# CPU_DRAM.net
KiCad netlist of a schematic drawn in Altium Designer
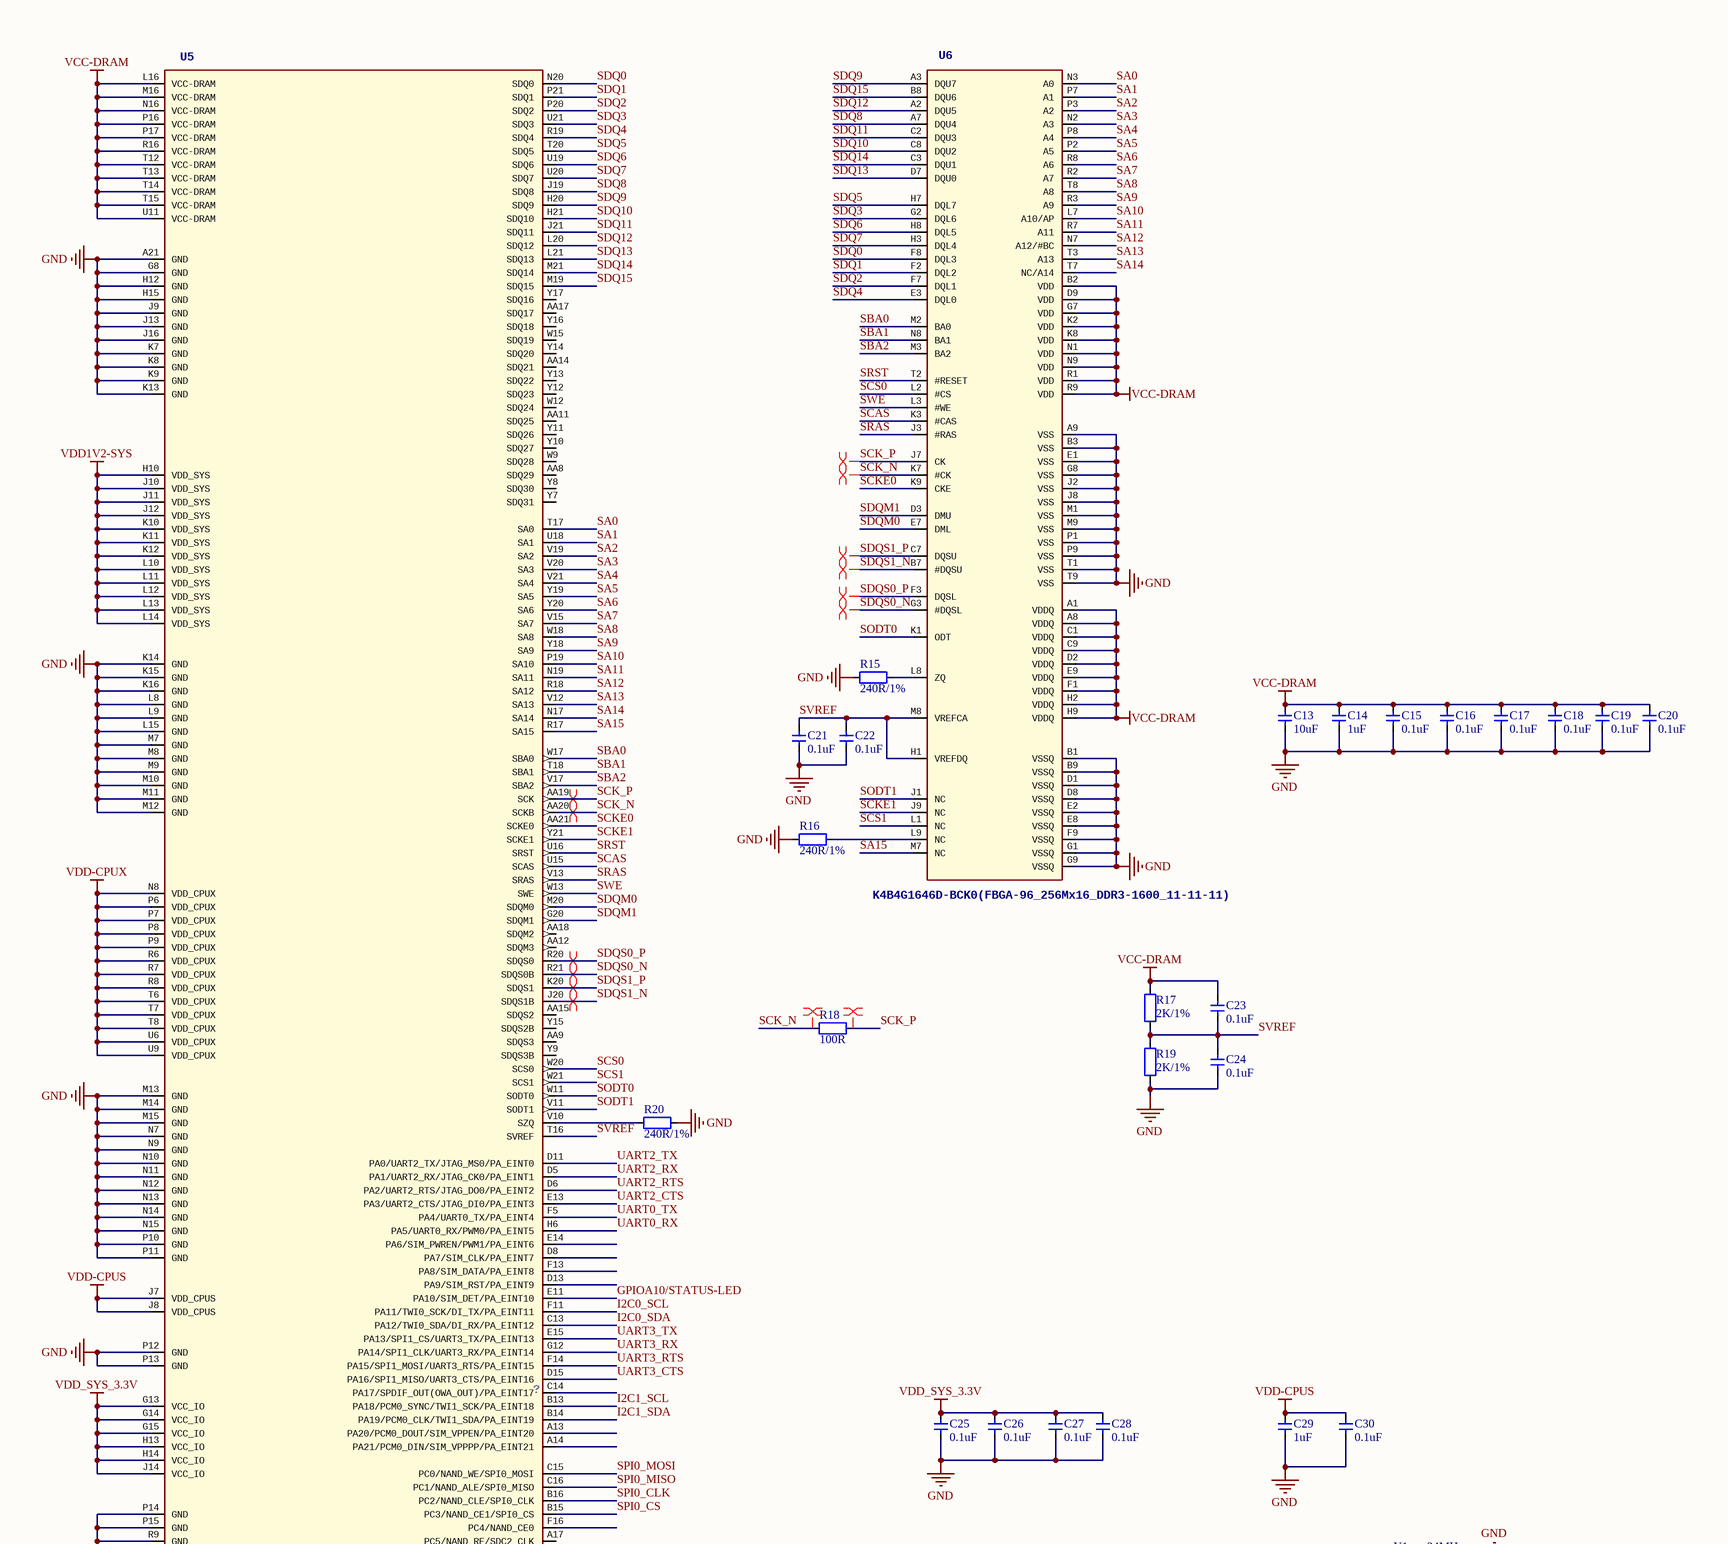
[diagram p0: CPU&DRAM.SchDoc, top]
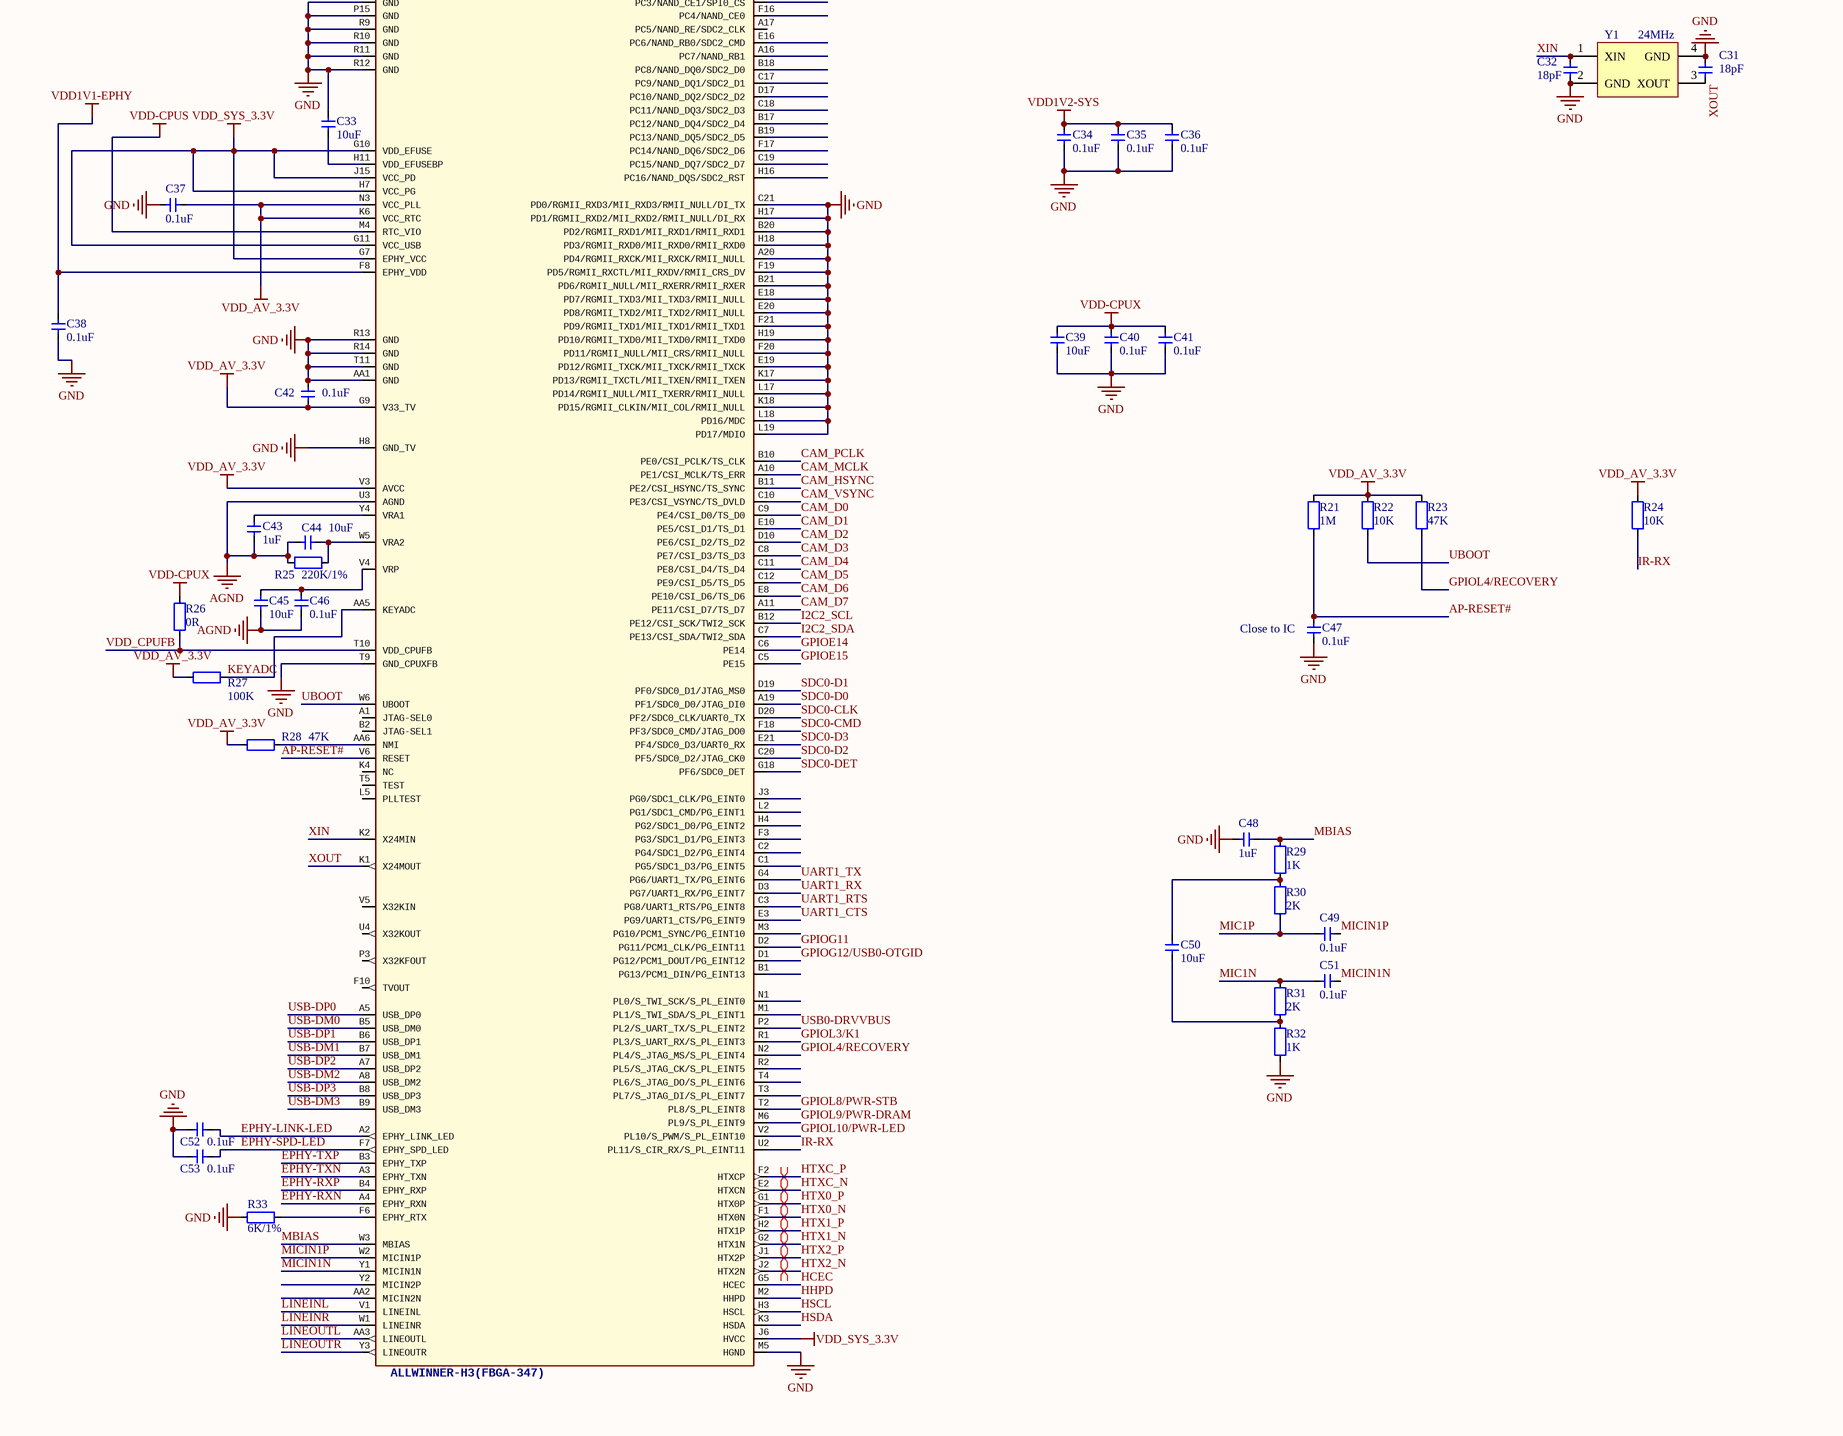
[diagram p1: CPU&DRAM.SchDoc, bottom]

(export (version "E")
  (design (tool "Eeschema 10.0.6"))
  (components
    (comp (ref "C13")
      (value "10uF")
      (footprint "CAP_0402")
      (description "Capacitor")
      (libsource (lib "MyPcbLib") (part "电容-0402"))
    )
    (comp (ref "C14")
      (value "1uF")
      (footprint "CAP_0402")
      (description "Capacitor")
      (libsource (lib "MyPcbLib") (part "电容-0402"))
    )
    (comp (ref "C15")
      (value "0.1uF")
      (footprint "CAP_0402")
      (description "Capacitor")
      (libsource (lib "MyPcbLib") (part "电容-0402"))
    )
    (comp (ref "C16")
      (value "0.1uF")
      (footprint "CAP_0402")
      (description "Capacitor")
      (libsource (lib "MyPcbLib") (part "电容-0402"))
    )
    (comp (ref "C17")
      (value "0.1uF")
      (footprint "CAP_0402")
      (description "Capacitor")
      (libsource (lib "MyPcbLib") (part "电容-0402"))
    )
    (comp (ref "C18")
      (value "0.1uF")
      (footprint "CAP_0402")
      (description "Capacitor")
      (libsource (lib "MyPcbLib") (part "电容-0402"))
    )
    (comp (ref "C19")
      (value "0.1uF")
      (footprint "CAP_0402")
      (description "Capacitor")
      (libsource (lib "MyPcbLib") (part "电容-0402"))
    )
    (comp (ref "C20")
      (value "0.1uF")
      (footprint "CAP_0402")
      (description "Capacitor")
      (libsource (lib "MyPcbLib") (part "电容-0402"))
    )
    (comp (ref "C21")
      (value "0.1uF")
      (footprint "CAP_0402")
      (description "Capacitor")
      (libsource (lib "MyPcbLib") (part "电容-0402"))
    )
    (comp (ref "C22")
      (value "0.1uF")
      (footprint "CAP_0402")
      (description "Capacitor")
      (libsource (lib "MyPcbLib") (part "电容-0402"))
    )
    (comp (ref "C23")
      (value "0.1uF")
      (footprint "CAP_0402")
      (description "Capacitor")
      (libsource (lib "MyPcbLib") (part "电容-0402"))
    )
    (comp (ref "C24")
      (value "0.1uF")
      (footprint "CAP_0402")
      (description "Capacitor")
      (libsource (lib "MyPcbLib") (part "电容-0402"))
    )
    (comp (ref "C25")
      (value "0.1uF")
      (footprint "CAP_0402")
      (description "Capacitor")
      (libsource (lib "MyPcbLib") (part "电容-0402"))
    )
    (comp (ref "C26")
      (value "0.1uF")
      (footprint "CAP_0402")
      (description "Capacitor")
      (libsource (lib "MyPcbLib") (part "电容-0402"))
    )
    (comp (ref "C27")
      (value "0.1uF")
      (footprint "CAP_0402")
      (description "Capacitor")
      (libsource (lib "MyPcbLib") (part "电容-0402"))
    )
    (comp (ref "C28")
      (value "0.1uF")
      (footprint "CAP_0402")
      (description "Capacitor")
      (libsource (lib "MyPcbLib") (part "电容-0402"))
    )
    (comp (ref "C29")
      (value "1uF")
      (footprint "CAP_0402")
      (description "Capacitor")
      (libsource (lib "MyPcbLib") (part "电容-0402"))
    )
    (comp (ref "C30")
      (value "0.1uF")
      (footprint "CAP_0402")
      (description "Capacitor")
      (libsource (lib "MyPcbLib") (part "电容-0402"))
    )
    (comp (ref "C31")
      (value "18pF")
      (footprint "CAP_0402")
      (description "Capacitor")
      (libsource (lib "MyPcbLib") (part "电容-0402"))
    )
    (comp (ref "C32")
      (value "18pF")
      (footprint "CAP_0402")
      (description "Capacitor")
      (libsource (lib "MyPcbLib") (part "电容-0402"))
    )
    (comp (ref "C33")
      (value "10uF")
      (footprint "CAP_0402")
      (description "Capacitor")
      (libsource (lib "MyPcbLib") (part "电容-0402"))
    )
    (comp (ref "C34")
      (value "0.1uF")
      (footprint "CAP_0402")
      (description "Capacitor")
      (libsource (lib "MyPcbLib") (part "电容-0402"))
    )
    (comp (ref "C35")
      (value "0.1uF")
      (footprint "CAP_0402")
      (description "Capacitor")
      (libsource (lib "MyPcbLib") (part "电容-0402"))
    )
    (comp (ref "C36")
      (value "0.1uF")
      (footprint "CAP_0402")
      (description "Capacitor")
      (libsource (lib "MyPcbLib") (part "电容-0402"))
    )
    (comp (ref "C37")
      (value "0.1uF")
      (footprint "CAP_0402")
      (description "Capacitor")
      (libsource (lib "MyPcbLib") (part "电容-0402"))
    )
    (comp (ref "C38")
      (value "0.1uF")
      (footprint "CAP_0402")
      (description "Capacitor")
      (libsource (lib "MyPcbLib") (part "电容-0402"))
    )
    (comp (ref "C39")
      (value "10uF")
      (footprint "CAP_0402")
      (description "Capacitor")
      (libsource (lib "MyPcbLib") (part "电容-0402"))
    )
    (comp (ref "C40")
      (value "0.1uF")
      (footprint "CAP_0402")
      (description "Capacitor")
      (libsource (lib "MyPcbLib") (part "电容-0402"))
    )
    (comp (ref "C41")
      (value "0.1uF")
      (footprint "CAP_0402")
      (description "Capacitor")
      (libsource (lib "MyPcbLib") (part "电容-0402"))
    )
    (comp (ref "C42")
      (value "0.1uF")
      (footprint "CAP_0402")
      (description "Capacitor")
      (libsource (lib "MyPcbLib") (part "电容-0402"))
    )
    (comp (ref "C43")
      (value "1uF")
      (footprint "CAP_0402")
      (description "Capacitor")
      (libsource (lib "MyPcbLib") (part "电容-0402"))
    )
    (comp (ref "C44")
      (value "10uF")
      (footprint "CAP_0402")
      (description "Capacitor")
      (libsource (lib "MyPcbLib") (part "电容-0402"))
    )
    (comp (ref "C45")
      (value "10uF")
      (footprint "CAP_0402")
      (description "Capacitor")
      (libsource (lib "MyPcbLib") (part "电容-0402"))
    )
    (comp (ref "C46")
      (value "0.1uF")
      (footprint "CAP_0402")
      (description "Capacitor")
      (libsource (lib "MyPcbLib") (part "电容-0402"))
    )
    (comp (ref "C47")
      (value "0.1uF")
      (footprint "CAP_0402")
      (description "Capacitor")
      (libsource (lib "MyPcbLib") (part "电容-0402"))
    )
    (comp (ref "C48")
      (value "1uF")
      (footprint "CAP_0402")
      (description "Capacitor")
      (libsource (lib "MyPcbLib") (part "电容-0402"))
    )
    (comp (ref "C49")
      (value "0.1uF")
      (footprint "CAP_0402")
      (description "Capacitor")
      (libsource (lib "MyPcbLib") (part "电容-0402"))
    )
    (comp (ref "C50")
      (value "10uF")
      (footprint "CAP_0402")
      (description "Capacitor")
      (libsource (lib "MyPcbLib") (part "电容-0402"))
    )
    (comp (ref "C51")
      (value "0.1uF")
      (footprint "CAP_0402")
      (description "Capacitor")
      (libsource (lib "MyPcbLib") (part "电容-0402"))
    )
    (comp (ref "C52")
      (value "0.1uF")
      (footprint "CAP_0402")
      (description "Capacitor")
      (libsource (lib "MyPcbLib") (part "电容-0402"))
    )
    (comp (ref "C53")
      (value "0.1uF")
      (footprint "CAP_0402")
      (description "Capacitor")
      (libsource (lib "MyPcbLib") (part "电容-0402"))
    )
    (comp (ref "R15")
      (value "240R/1%")
      (footprint "RES_0402")
      (description "Resistor")
      (libsource (lib "") (part "电阻-0402_2"))
    )
    (comp (ref "R16")
      (value "240R/1%")
      (footprint "RES_0402")
      (description "Resistor")
      (libsource (lib "") (part "电阻-0402_2"))
    )
    (comp (ref "R17")
      (value "2K/1%")
      (footprint "RES_0402")
      (description "Resistor")
      (libsource (lib "MyPcbLib") (part "电阻-0402"))
    )
    (comp (ref "R18")
      (value "100R")
      (footprint "RES_0402")
      (description "Resistor")
      (libsource (lib "") (part "电阻-0402_1"))
    )
    (comp (ref "R19")
      (value "2K/1%")
      (footprint "RES_0402")
      (description "Resistor")
      (libsource (lib "MyPcbLib") (part "电阻-0402"))
    )
    (comp (ref "R20")
      (value "240R/1%")
      (footprint "RES_0402")
      (description "Resistor")
      (libsource (lib "") (part "电阻-0402_1"))
    )
    (comp (ref "R21")
      (value "1M")
      (footprint "RES_0402")
      (description "Resistor")
      (libsource (lib "MyPcbLib") (part "电阻-0402"))
    )
    (comp (ref "R22")
      (value "10K")
      (footprint "RES_0402")
      (description "Resistor")
      (libsource (lib "MyPcbLib") (part "电阻-0402"))
    )
    (comp (ref "R23")
      (value "47K")
      (footprint "RES_0402")
      (description "Resistor")
      (libsource (lib "MyPcbLib") (part "电阻-0402"))
    )
    (comp (ref "R24")
      (value "10K")
      (footprint "RES_0402")
      (description "Resistor")
      (libsource (lib "MyPcbLib") (part "电阻-0402"))
    )
    (comp (ref "R25")
      (value "220K/1%")
      (footprint "RES_0402")
      (description "Resistor")
      (libsource (lib "") (part "电阻-0402_1"))
    )
    (comp (ref "R26")
      (value "0R")
      (footprint "RES_0402")
      (description "Resistor")
      (libsource (lib "MyPcbLib") (part "电阻-0402"))
    )
    (comp (ref "R27")
      (value "100K")
      (footprint "RES_0402")
      (description "Resistor")
      (libsource (lib "") (part "电阻-0402_1"))
    )
    (comp (ref "R28")
      (value "47K")
      (footprint "RES_0402")
      (description "Resistor")
      (libsource (lib "") (part "电阻-0402_1"))
    )
    (comp (ref "R29")
      (value "1K")
      (footprint "RES_0402")
      (description "Resistor")
      (libsource (lib "MyPcbLib") (part "电阻-0402"))
    )
    (comp (ref "R30")
      (value "2K")
      (footprint "RES_0402")
      (description "Resistor")
      (libsource (lib "MyPcbLib") (part "电阻-0402"))
    )
    (comp (ref "R31")
      (value "2K")
      (footprint "RES_0402")
      (description "Resistor")
      (libsource (lib "MyPcbLib") (part "电阻-0402"))
    )
    (comp (ref "R32")
      (value "1K")
      (footprint "RES_0402")
      (description "Resistor")
      (libsource (lib "MyPcbLib") (part "电阻-0402"))
    )
    (comp (ref "R33")
      (value "6K/1%")
      (footprint "RES_0402")
      (description "Resistor")
      (libsource (lib "") (part "电阻-0402_1"))
    )
    (comp (ref "U5")
      (value "ALLWINNER-H3(FBGA-347)")
      (footprint "FBGA-347")
      (fields (field (name "?") "?"))
      (libsource (lib "mLib") (part "ALLWINNER-H3(FBGA-347)"))
    )
    (comp (ref "U6")
      (value "K4B4G1646D-BCK0(FBGA-96_256Mx16_DDR3-1600_11-11-11)")
      (footprint "FBGA96(HYNIX_SAMSUNG_512MX16_DDR3)")
      (libsource (lib "mLib") (part "K4B8G1646Q-MYK0(FBGA-96_512MX16_DDR3-1600)"))
    )
    (comp (ref "Y1")
      (value "24MHz")
      (footprint "晶振2520")
      (description "2520无源")
      (fields (field (name "MF") "ECS International") (field (name "MP") "ECS-3225S30-240-EN-TR"))
      (libsource (lib "MyPcbLib") (part "晶振-4Pin-无源"))
    )
  )
  (nets
    (net (code "1") (name "/AP-RESET#") (class "Default")
      (node (ref "C47") (pin "2") (pinfunction "2_2") (pintype "passive"))
      (node (ref "R21") (pin "1") (pinfunction "1_1") (pintype "passive"))
      (node (ref "U5") (pin "V6") (pinfunction "RESET_V6") (pintype "passive"))
    )
    (net (code "2") (name "/CAM_D0") (class "Default")
      (node (ref "U5") (pin "C9") (pinfunction "PE4/CSI_D0/TS_D0_C9") (pintype "passive"))
    )
    (net (code "3") (name "/CAM_D1") (class "Default")
      (node (ref "U5") (pin "E10") (pinfunction "PE5/CSI_D1/TS_D1_E10") (pintype "passive"))
    )
    (net (code "4") (name "/CAM_D2") (class "Default")
      (node (ref "U5") (pin "D10") (pinfunction "PE6/CSI_D2/TS_D2_D10") (pintype "passive"))
    )
    (net (code "5") (name "/CAM_D3") (class "Default")
      (node (ref "U5") (pin "C8") (pinfunction "PE7/CSI_D3/TS_D3_C8") (pintype "passive"))
    )
    (net (code "6") (name "/CAM_D4") (class "Default")
      (node (ref "U5") (pin "C11") (pinfunction "PE8/CSI_D4/TS_D4_C11") (pintype "passive"))
    )
    (net (code "7") (name "/CAM_D5") (class "Default")
      (node (ref "U5") (pin "C12") (pinfunction "PE9/CSI_D5/TS_D5_C12") (pintype "passive"))
    )
    (net (code "8") (name "/CAM_D6") (class "Default")
      (node (ref "U5") (pin "E8") (pinfunction "PE10/CSI_D6/TS_D6_E8") (pintype "passive"))
    )
    (net (code "9") (name "/CAM_D7") (class "Default")
      (node (ref "U5") (pin "A11") (pinfunction "PE11/CSI_D7/TS_D7_A11") (pintype "passive"))
    )
    (net (code "10") (name "/CAM_HSYNC") (class "Default")
      (node (ref "U5") (pin "B11") (pinfunction "PE2/CSI_HSYNC/TS_SYNC_B11") (pintype "passive"))
    )
    (net (code "11") (name "/CAM_MCLK") (class "Default")
      (node (ref "U5") (pin "A10") (pinfunction "PE1/CSI_MCLK/TS_ERR_A10") (pintype "passive"))
    )
    (net (code "12") (name "/CAM_PCLK") (class "Default")
      (node (ref "U5") (pin "B10") (pinfunction "PE0/CSI_PCLK/TS_CLK_B10") (pintype "passive"))
    )
    (net (code "13") (name "/CAM_VSYNC") (class "Default")
      (node (ref "U5") (pin "C10") (pinfunction "PE3/CSI_VSYNC/TS_DVLD_C10") (pintype "passive"))
    )
    (net (code "14") (name "/EPHY-LINK-LED") (class "Default")
      (node (ref "C52") (pin "2") (pinfunction "2_2") (pintype "passive"))
      (node (ref "U5") (pin "A2") (pinfunction "EPHY_LINK_LED_A2") (pintype "output"))
    )
    (net (code "15") (name "/EPHY-RXN") (class "Default")
      (node (ref "U5") (pin "A4") (pinfunction "EPHY_RXN_A4") (pintype "passive"))
    )
    (net (code "16") (name "/EPHY-RXP") (class "Default")
      (node (ref "U5") (pin "B4") (pinfunction "EPHY_RXP_B4") (pintype "passive"))
    )
    (net (code "17") (name "/EPHY-SPD-LED") (class "Default")
      (node (ref "C53") (pin "2") (pinfunction "2_2") (pintype "passive"))
      (node (ref "U5") (pin "F7") (pinfunction "EPHY_SPD_LED_F7") (pintype "output"))
    )
    (net (code "18") (name "/EPHY-TXN") (class "Default")
      (node (ref "U5") (pin "A3") (pinfunction "EPHY_TXN_A3") (pintype "passive"))
    )
    (net (code "19") (name "/EPHY-TXP") (class "Default")
      (node (ref "U5") (pin "B3") (pinfunction "EPHY_TXP_B3") (pintype "passive"))
    )
    (net (code "20") (name "/GPIOA10{slash}STATUS-LED") (class "Default")
      (node (ref "U5") (pin "E11") (pinfunction "PA10/SIM_DET/PA_EINT10_E11") (pintype "passive"))
    )
    (net (code "21") (name "/GPIOE14") (class "Default")
      (node (ref "U5") (pin "C6") (pinfunction "PE14_C6") (pintype "passive"))
    )
    (net (code "22") (name "/GPIOE15") (class "Default")
      (node (ref "U5") (pin "C5") (pinfunction "PE15_C5") (pintype "passive"))
    )
    (net (code "23") (name "/GPIOG11") (class "Default")
      (node (ref "U5") (pin "D2") (pinfunction "PG11/PCM1_CLK/PG_EINT11_D2") (pintype "passive"))
    )
    (net (code "24") (name "/GPIOG12{slash}USB0-OTGID") (class "Default")
      (node (ref "U5") (pin "D1") (pinfunction "PG12/PCM1_DOUT/PG_EINT12_D1") (pintype "passive"))
    )
    (net (code "25") (name "/GPIOL3{slash}K1") (class "Default")
      (node (ref "U5") (pin "R1") (pinfunction "PL3/S_UART_RX/S_PL_EINT3_R1") (pintype "passive"))
    )
    (net (code "26") (name "/GPIOL4{slash}RECOVERY") (class "Default")
      (node (ref "R23") (pin "1") (pinfunction "1_1") (pintype "passive"))
      (node (ref "U5") (pin "N2") (pinfunction "PL4/S_JTAG_MS/S_PL_EINT4_N2") (pintype "passive"))
    )
    (net (code "27") (name "/GPIOL8{slash}PWR-STB") (class "Default")
      (node (ref "U5") (pin "T2") (pinfunction "PL8/S_PL_EINT8_T2") (pintype "passive"))
    )
    (net (code "28") (name "/GPIOL9{slash}PWR-DRAM") (class "Default")
      (node (ref "U5") (pin "M6") (pinfunction "PL9/S_PL_EINT9_M6") (pintype "passive"))
    )
    (net (code "29") (name "/GPIOL10{slash}PWR-LED") (class "Default")
      (node (ref "U5") (pin "V2") (pinfunction "PL10/S_PWM/S_PL_EINT10_V2") (pintype "passive"))
    )
    (net (code "30") (name "/HCEC") (class "Default")
      (node (ref "U5") (pin "G5") (pinfunction "HCEC_G5") (pintype "passive"))
    )
    (net (code "31") (name "/HHPD") (class "Default")
      (node (ref "U5") (pin "M2") (pinfunction "HHPD_M2") (pintype "passive"))
    )
    (net (code "32") (name "/HSCL") (class "Default")
      (node (ref "U5") (pin "H3") (pinfunction "HSCL_H3") (pintype "output"))
    )
    (net (code "33") (name "/HSDA") (class "Default")
      (node (ref "U5") (pin "K3") (pinfunction "HSDA_K3") (pintype "passive"))
    )
    (net (code "34") (name "/HTX0_N") (class "Default")
      (node (ref "U5") (pin "F1") (pinfunction "HTX0N_F1") (pintype "output"))
    )
    (net (code "35") (name "/HTX0_P") (class "Default")
      (node (ref "U5") (pin "G1") (pinfunction "HTX0P_G1") (pintype "output"))
    )
    (net (code "36") (name "/HTX1_N") (class "Default")
      (node (ref "U5") (pin "G2") (pinfunction "HTX1N_G2") (pintype "output"))
    )
    (net (code "37") (name "/HTX1_P") (class "Default")
      (node (ref "U5") (pin "H2") (pinfunction "HTX1P_H2") (pintype "output"))
    )
    (net (code "38") (name "/HTX2_N") (class "Default")
      (node (ref "U5") (pin "J2") (pinfunction "HTX2N_J2") (pintype "output"))
    )
    (net (code "39") (name "/HTX2_P") (class "Default")
      (node (ref "U5") (pin "J1") (pinfunction "HTX2P_J1") (pintype "output"))
    )
    (net (code "40") (name "/HTXC_N") (class "Default")
      (node (ref "U5") (pin "E2") (pinfunction "HTXCN_E2") (pintype "output"))
    )
    (net (code "41") (name "/HTXC_P") (class "Default")
      (node (ref "U5") (pin "F2") (pinfunction "HTXCP_F2") (pintype "output"))
    )
    (net (code "42") (name "/I2C0_SCL") (class "Default")
      (node (ref "U5") (pin "F11") (pinfunction "PA11/TWI0_SCK/DI_TX/PA_EINT11_F11") (pintype "passive"))
    )
    (net (code "43") (name "/I2C0_SDA") (class "Default")
      (node (ref "U5") (pin "C13") (pinfunction "PA12/TWI0_SDA/DI_RX/PA_EINT12_C13") (pintype "passive"))
    )
    (net (code "44") (name "/I2C1_SCL") (class "Default")
      (node (ref "U5") (pin "B13") (pinfunction "PA18/PCM0_SYNC/TWI1_SCK/PA_EINT18_B13") (pintype "passive"))
    )
    (net (code "45") (name "/I2C1_SDA") (class "Default")
      (node (ref "U5") (pin "B14") (pinfunction "PA19/PCM0_CLK/TWI1_SDA/PA_EINT19_B14") (pintype "passive"))
    )
    (net (code "46") (name "/I2C2_SCL") (class "Default")
      (node (ref "U5") (pin "B12") (pinfunction "PE12/CSI_SCK/TWI2_SCK_B12") (pintype "passive"))
    )
    (net (code "47") (name "/I2C2_SDA") (class "Default")
      (node (ref "U5") (pin "C7") (pinfunction "PE13/CSI_SDA/TWI2_SDA_C7") (pintype "passive"))
    )
    (net (code "48") (name "/IR-RX") (class "Default")
      (node (ref "R24") (pin "1") (pinfunction "1_1") (pintype "passive"))
      (node (ref "U5") (pin "U2") (pinfunction "PL11/S_CIR_RX/S_PL_EINT11_U2") (pintype "passive"))
    )
    (net (code "49") (name "/KEYADC") (class "Default")
      (node (ref "R27") (pin "2") (pinfunction "2_2") (pintype "passive"))
      (node (ref "U5") (pin "AA5") (pinfunction "KEYADC_AA5") (pintype "passive"))
    )
    (net (code "50") (name "/LINEINL") (class "Default")
      (node (ref "U5") (pin "V1") (pinfunction "LINEINL_V1") (pintype "passive"))
    )
    (net (code "51") (name "/LINEINR") (class "Default")
      (node (ref "U5") (pin "W1") (pinfunction "LINEINR_W1") (pintype "passive"))
    )
    (net (code "52") (name "/LINEOUTL") (class "Default")
      (node (ref "U5") (pin "AA3") (pinfunction "LINEOUTL_AA3") (pintype "output"))
    )
    (net (code "53") (name "/LINEOUTR") (class "Default")
      (node (ref "U5") (pin "Y3") (pinfunction "LINEOUTR_Y3") (pintype "output"))
    )
    (net (code "54") (name "/MBIAS") (class "Default")
      (node (ref "C48") (pin "1") (pinfunction "1_1") (pintype "passive"))
      (node (ref "R29") (pin "2") (pinfunction "2_2") (pintype "passive"))
      (node (ref "U5") (pin "W3") (pinfunction "MBIAS_W3") (pintype "passive"))
    )
    (net (code "55") (name "/MIC1N") (class "Default")
      (node (ref "C51") (pin "2") (pinfunction "2_2") (pintype "passive"))
      (node (ref "R31") (pin "2") (pinfunction "2_2") (pintype "passive"))
    )
    (net (code "56") (name "/MIC1P") (class "Default")
      (node (ref "C49") (pin "2") (pinfunction "2_2") (pintype "passive"))
      (node (ref "R30") (pin "1") (pinfunction "1_1") (pintype "passive"))
    )
    (net (code "57") (name "/MICIN1N") (class "Default")
      (node (ref "C51") (pin "1") (pinfunction "1_1") (pintype "passive"))
      (node (ref "U5") (pin "Y1") (pinfunction "MICIN1N_Y1") (pintype "passive"))
    )
    (net (code "58") (name "/MICIN1P") (class "Default")
      (node (ref "C49") (pin "1") (pinfunction "1_1") (pintype "passive"))
      (node (ref "U5") (pin "W2") (pinfunction "MICIN1P_W2") (pintype "passive"))
    )
    (net (code "59") (name "/SA0") (class "Default")
      (node (ref "U5") (pin "T17") (pinfunction "SA0_T17") (pintype "passive"))
      (node (ref "U6") (pin "N3") (pinfunction "A0_N3") (pintype "passive"))
    )
    (net (code "60") (name "/SA1") (class "Default")
      (node (ref "U5") (pin "U18") (pinfunction "SA1_U18") (pintype "passive"))
      (node (ref "U6") (pin "P7") (pinfunction "A1_P7") (pintype "passive"))
    )
    (net (code "61") (name "/SA2") (class "Default")
      (node (ref "U5") (pin "V19") (pinfunction "SA2_V19") (pintype "passive"))
      (node (ref "U6") (pin "P3") (pinfunction "A2_P3") (pintype "passive"))
    )
    (net (code "62") (name "/SA3") (class "Default")
      (node (ref "U5") (pin "V20") (pinfunction "SA3_V20") (pintype "passive"))
      (node (ref "U6") (pin "N2") (pinfunction "A3_N2") (pintype "passive"))
    )
    (net (code "63") (name "/SA4") (class "Default")
      (node (ref "U5") (pin "V21") (pinfunction "SA4_V21") (pintype "passive"))
      (node (ref "U6") (pin "P8") (pinfunction "A4_P8") (pintype "passive"))
    )
    (net (code "64") (name "/SA5") (class "Default")
      (node (ref "U5") (pin "Y19") (pinfunction "SA5_Y19") (pintype "passive"))
      (node (ref "U6") (pin "P2") (pinfunction "A5_P2") (pintype "passive"))
    )
    (net (code "65") (name "/SA6") (class "Default")
      (node (ref "U5") (pin "Y20") (pinfunction "SA6_Y20") (pintype "passive"))
      (node (ref "U6") (pin "R8") (pinfunction "A6_R8") (pintype "passive"))
    )
    (net (code "66") (name "/SA7") (class "Default")
      (node (ref "U5") (pin "V15") (pinfunction "SA7_V15") (pintype "passive"))
      (node (ref "U6") (pin "R2") (pinfunction "A7_R2") (pintype "passive"))
    )
    (net (code "67") (name "/SA8") (class "Default")
      (node (ref "U5") (pin "W18") (pinfunction "SA8_W18") (pintype "passive"))
      (node (ref "U6") (pin "T8") (pinfunction "A8_T8") (pintype "passive"))
    )
    (net (code "68") (name "/SA9") (class "Default")
      (node (ref "U5") (pin "Y18") (pinfunction "SA9_Y18") (pintype "passive"))
      (node (ref "U6") (pin "R3") (pinfunction "A9_R3") (pintype "passive"))
    )
    (net (code "69") (name "/SA10") (class "Default")
      (node (ref "U5") (pin "P19") (pinfunction "SA10_P19") (pintype "passive"))
      (node (ref "U6") (pin "L7") (pinfunction "A10/AP_L7") (pintype "passive"))
    )
    (net (code "70") (name "/SA11") (class "Default")
      (node (ref "U5") (pin "N19") (pinfunction "SA11_N19") (pintype "passive"))
      (node (ref "U6") (pin "R7") (pinfunction "A11_R7") (pintype "passive"))
    )
    (net (code "71") (name "/SA12") (class "Default")
      (node (ref "U5") (pin "R18") (pinfunction "SA12_R18") (pintype "passive"))
      (node (ref "U6") (pin "N7") (pinfunction "A12/#BC_N7") (pintype "passive"))
    )
    (net (code "72") (name "/SA13") (class "Default")
      (node (ref "U5") (pin "V12") (pinfunction "SA13_V12") (pintype "passive"))
      (node (ref "U6") (pin "T3") (pinfunction "A13_T3") (pintype "passive"))
    )
    (net (code "73") (name "/SA14") (class "Default")
      (node (ref "U5") (pin "N17") (pinfunction "SA14_N17") (pintype "passive"))
      (node (ref "U6") (pin "T7") (pinfunction "NC/A14_T7") (pintype "passive"))
    )
    (net (code "74") (name "/SA15") (class "Default")
      (node (ref "U5") (pin "R17") (pinfunction "SA15_R17") (pintype "passive"))
      (node (ref "U6") (pin "M7") (pinfunction "NC_M7") (pintype "passive"))
    )
    (net (code "75") (name "/SBA0") (class "Default")
      (node (ref "U5") (pin "W17") (pinfunction "SBA0_W17") (pintype "output"))
      (node (ref "U6") (pin "M2") (pinfunction "BA0_M2") (pintype "passive"))
    )
    (net (code "76") (name "/SBA1") (class "Default")
      (node (ref "U5") (pin "T18") (pinfunction "SBA1_T18") (pintype "output"))
      (node (ref "U6") (pin "N8") (pinfunction "BA1_N8") (pintype "passive"))
    )
    (net (code "77") (name "/SBA2") (class "Default")
      (node (ref "U5") (pin "V17") (pinfunction "SBA2_V17") (pintype "output"))
      (node (ref "U6") (pin "M3") (pinfunction "BA2_M3") (pintype "passive"))
    )
    (net (code "78") (name "/SCAS") (class "Default")
      (node (ref "U5") (pin "U15") (pinfunction "SCAS_U15") (pintype "output"))
      (node (ref "U6") (pin "K3") (pinfunction "#CAS_K3") (pintype "passive"))
    )
    (net (code "79") (name "/SCKE0") (class "Default")
      (node (ref "U5") (pin "AA21") (pinfunction "SCKE0_AA21") (pintype "output"))
      (node (ref "U6") (pin "K9") (pinfunction "CKE_K9") (pintype "passive"))
    )
    (net (code "80") (name "/SCKE1") (class "Default")
      (node (ref "U5") (pin "Y21") (pinfunction "SCKE1_Y21") (pintype "output"))
      (node (ref "U6") (pin "J9") (pinfunction "NC_J9") (pintype "passive"))
    )
    (net (code "81") (name "/SCK_N") (class "Default")
      (node (ref "R18") (pin "1") (pinfunction "1_1") (pintype "passive"))
      (node (ref "U5") (pin "AA20") (pinfunction "SCKB_AA20") (pintype "output"))
      (node (ref "U6") (pin "K7") (pinfunction "#CK_K7") (pintype "passive"))
    )
    (net (code "82") (name "/SCK_P") (class "Default")
      (node (ref "R18") (pin "2") (pinfunction "2_2") (pintype "passive"))
      (node (ref "U5") (pin "AA19") (pinfunction "SCK_AA19") (pintype "output"))
      (node (ref "U6") (pin "J7") (pinfunction "CK_J7") (pintype "passive"))
    )
    (net (code "83") (name "/SCS0") (class "Default")
      (node (ref "U5") (pin "W20") (pinfunction "SCS0_W20") (pintype "output"))
      (node (ref "U6") (pin "L2") (pinfunction "#CS_L2") (pintype "passive"))
    )
    (net (code "84") (name "/SCS1") (class "Default")
      (node (ref "U5") (pin "W21") (pinfunction "SCS1_W21") (pintype "output"))
      (node (ref "U6") (pin "L1") (pinfunction "NC_L1") (pintype "passive"))
    )
    (net (code "85") (name "/SDC0-CLK") (class "Default")
      (node (ref "U5") (pin "D20") (pinfunction "PF2/SDC0_CLK/UART0_TX_D20") (pintype "passive"))
    )
    (net (code "86") (name "/SDC0-CMD") (class "Default")
      (node (ref "U5") (pin "F18") (pinfunction "PF3/SDC0_CMD/JTAG_DO0_F18") (pintype "passive"))
    )
    (net (code "87") (name "/SDC0-D0") (class "Default")
      (node (ref "U5") (pin "A19") (pinfunction "PF1/SDC0_D0/JTAG_DI0_A19") (pintype "passive"))
    )
    (net (code "88") (name "/SDC0-D1") (class "Default")
      (node (ref "U5") (pin "D19") (pinfunction "PF0/SDC0_D1/JTAG_MS0_D19") (pintype "passive"))
    )
    (net (code "89") (name "/SDC0-D2") (class "Default")
      (node (ref "U5") (pin "C20") (pinfunction "PF5/SDC0_D2/JTAG_CK0_C20") (pintype "passive"))
    )
    (net (code "90") (name "/SDC0-D3") (class "Default")
      (node (ref "U5") (pin "E21") (pinfunction "PF4/SDC0_D3/UART0_RX_E21") (pintype "passive"))
    )
    (net (code "91") (name "/SDC0-DET") (class "Default")
      (node (ref "U5") (pin "G18") (pinfunction "PF6/SDC0_DET_G18") (pintype "passive"))
    )
    (net (code "92") (name "/SDQ0") (class "Default")
      (node (ref "U5") (pin "N20") (pinfunction "SDQ0_N20") (pintype "passive"))
      (node (ref "U6") (pin "F8") (pinfunction "DQL3_F8") (pintype "passive"))
    )
    (net (code "93") (name "/SDQ1") (class "Default")
      (node (ref "U5") (pin "P21") (pinfunction "SDQ1_P21") (pintype "passive"))
      (node (ref "U6") (pin "F2") (pinfunction "DQL2_F2") (pintype "passive"))
    )
    (net (code "94") (name "/SDQ2") (class "Default")
      (node (ref "U5") (pin "P20") (pinfunction "SDQ2_P20") (pintype "passive"))
      (node (ref "U6") (pin "F7") (pinfunction "DQL1_F7") (pintype "passive"))
    )
    (net (code "95") (name "/SDQ3") (class "Default")
      (node (ref "U5") (pin "U21") (pinfunction "SDQ3_U21") (pintype "passive"))
      (node (ref "U6") (pin "G2") (pinfunction "DQL6_G2") (pintype "passive"))
    )
    (net (code "96") (name "/SDQ4") (class "Default")
      (node (ref "U5") (pin "R19") (pinfunction "SDQ4_R19") (pintype "passive"))
      (node (ref "U6") (pin "E3") (pinfunction "DQL0_E3") (pintype "passive"))
    )
    (net (code "97") (name "/SDQ5") (class "Default")
      (node (ref "U5") (pin "T20") (pinfunction "SDQ5_T20") (pintype "passive"))
      (node (ref "U6") (pin "H7") (pinfunction "DQL7_H7") (pintype "passive"))
    )
    (net (code "98") (name "/SDQ6") (class "Default")
      (node (ref "U5") (pin "U19") (pinfunction "SDQ6_U19") (pintype "passive"))
      (node (ref "U6") (pin "H8") (pinfunction "DQL5_H8") (pintype "passive"))
    )
    (net (code "99") (name "/SDQ7") (class "Default")
      (node (ref "U5") (pin "U20") (pinfunction "SDQ7_U20") (pintype "passive"))
      (node (ref "U6") (pin "H3") (pinfunction "DQL4_H3") (pintype "passive"))
    )
    (net (code "100") (name "/SDQ8") (class "Default")
      (node (ref "U5") (pin "J19") (pinfunction "SDQ8_J19") (pintype "passive"))
      (node (ref "U6") (pin "A7") (pinfunction "DQU4_A7") (pintype "passive"))
    )
    (net (code "101") (name "/SDQ9") (class "Default")
      (node (ref "U5") (pin "H20") (pinfunction "SDQ9_H20") (pintype "passive"))
      (node (ref "U6") (pin "A3") (pinfunction "DQU7_A3") (pintype "passive"))
    )
    (net (code "102") (name "/SDQ10") (class "Default")
      (node (ref "U5") (pin "H21") (pinfunction "SDQ10_H21") (pintype "passive"))
      (node (ref "U6") (pin "C8") (pinfunction "DQU2_C8") (pintype "passive"))
    )
    (net (code "103") (name "/SDQ11") (class "Default")
      (node (ref "U5") (pin "J21") (pinfunction "SDQ11_J21") (pintype "passive"))
      (node (ref "U6") (pin "C2") (pinfunction "DQU3_C2") (pintype "passive"))
    )
    (net (code "104") (name "/SDQ12") (class "Default")
      (node (ref "U5") (pin "L20") (pinfunction "SDQ12_L20") (pintype "passive"))
      (node (ref "U6") (pin "A2") (pinfunction "DQU5_A2") (pintype "passive"))
    )
    (net (code "105") (name "/SDQ13") (class "Default")
      (node (ref "U5") (pin "L21") (pinfunction "SDQ13_L21") (pintype "passive"))
      (node (ref "U6") (pin "D7") (pinfunction "DQU0_D7") (pintype "passive"))
    )
    (net (code "106") (name "/SDQ14") (class "Default")
      (node (ref "U5") (pin "M21") (pinfunction "SDQ14_M21") (pintype "passive"))
      (node (ref "U6") (pin "C3") (pinfunction "DQU1_C3") (pintype "passive"))
    )
    (net (code "107") (name "/SDQ15") (class "Default")
      (node (ref "U5") (pin "M19") (pinfunction "SDQ15_M19") (pintype "passive"))
      (node (ref "U6") (pin "B8") (pinfunction "DQU6_B8") (pintype "passive"))
    )
    (net (code "108") (name "/SDQM0") (class "Default")
      (node (ref "U5") (pin "M20") (pinfunction "SDQM0_M20") (pintype "output"))
      (node (ref "U6") (pin "E7") (pinfunction "DML_E7") (pintype "passive"))
    )
    (net (code "109") (name "/SDQM1") (class "Default")
      (node (ref "U5") (pin "G20") (pinfunction "SDQM1_G20") (pintype "output"))
      (node (ref "U6") (pin "D3") (pinfunction "DMU_D3") (pintype "passive"))
    )
    (net (code "110") (name "/SDQS0_N") (class "Default")
      (node (ref "U5") (pin "R21") (pinfunction "SDQS0B_R21") (pintype "passive"))
      (node (ref "U6") (pin "G3") (pinfunction "#DQSL_G3") (pintype "passive"))
    )
    (net (code "111") (name "/SDQS0_P") (class "Default")
      (node (ref "U5") (pin "R20") (pinfunction "SDQS0_R20") (pintype "passive"))
      (node (ref "U6") (pin "F3") (pinfunction "DQSL_F3") (pintype "passive"))
    )
    (net (code "112") (name "/SDQS1_N") (class "Default")
      (node (ref "U5") (pin "J20") (pinfunction "SDQS1B_J20") (pintype "passive"))
      (node (ref "U6") (pin "B7") (pinfunction "#DQSU_B7") (pintype "passive"))
    )
    (net (code "113") (name "/SDQS1_P") (class "Default")
      (node (ref "U5") (pin "K20") (pinfunction "SDQS1_K20") (pintype "passive"))
      (node (ref "U6") (pin "C7") (pinfunction "DQSU_C7") (pintype "passive"))
    )
    (net (code "114") (name "/SODT0") (class "Default")
      (node (ref "U5") (pin "W11") (pinfunction "SODT0_W11") (pintype "output"))
      (node (ref "U6") (pin "K1") (pinfunction "ODT_K1") (pintype "passive"))
    )
    (net (code "115") (name "/SODT1") (class "Default")
      (node (ref "U5") (pin "V11") (pinfunction "SODT1_V11") (pintype "output"))
      (node (ref "U6") (pin "J1") (pinfunction "NC_J1") (pintype "passive"))
    )
    (net (code "116") (name "/SPI0_CLK") (class "Default")
      (node (ref "U5") (pin "B16") (pinfunction "PC2/NAND_CLE/SPI0_CLK_B16") (pintype "passive"))
    )
    (net (code "117") (name "/SPI0_CS") (class "Default")
      (node (ref "U5") (pin "B15") (pinfunction "PC3/NAND_CE1/SPI0_CS_B15") (pintype "passive"))
    )
    (net (code "118") (name "/SPI0_MISO") (class "Default")
      (node (ref "U5") (pin "C16") (pinfunction "PC1/NAND_ALE/SPI0_MISO_C16") (pintype "passive"))
    )
    (net (code "119") (name "/SPI0_MOSI") (class "Default")
      (node (ref "U5") (pin "C15") (pinfunction "PC0/NAND_WE/SPI0_MOSI_C15") (pintype "passive"))
    )
    (net (code "120") (name "/SRAS") (class "Default")
      (node (ref "U5") (pin "V13") (pinfunction "SRAS_V13") (pintype "output"))
      (node (ref "U6") (pin "J3") (pinfunction "#RAS_J3") (pintype "passive"))
    )
    (net (code "121") (name "/SRST") (class "Default")
      (node (ref "U5") (pin "U16") (pinfunction "SRST_U16") (pintype "output"))
      (node (ref "U6") (pin "T2") (pinfunction "#RESET_T2") (pintype "passive"))
    )
    (net (code "122") (name "/SVREF") (class "Default")
      (node (ref "C21") (pin "2") (pinfunction "2_2") (pintype "passive"))
      (node (ref "C22") (pin "2") (pinfunction "2_2") (pintype "passive"))
      (node (ref "C23") (pin "1") (pinfunction "1_1") (pintype "passive"))
      (node (ref "C24") (pin "2") (pinfunction "2_2") (pintype "passive"))
      (node (ref "R17") (pin "1") (pinfunction "1_1") (pintype "passive"))
      (node (ref "R19") (pin "2") (pinfunction "2_2") (pintype "passive"))
      (node (ref "U5") (pin "T16") (pinfunction "SVREF_T16") (pintype "power_in"))
      (node (ref "U6") (pin "H1") (pinfunction "VREFDQ_H1") (pintype "passive"))
      (node (ref "U6") (pin "M8") (pinfunction "VREFCA_M8") (pintype "passive"))
    )
    (net (code "123") (name "/SWE") (class "Default")
      (node (ref "U5") (pin "W13") (pinfunction "SWE_W13") (pintype "output"))
      (node (ref "U6") (pin "L3") (pinfunction "#WE_L3") (pintype "passive"))
    )
    (net (code "124") (name "/UART0_RX") (class "Default")
      (node (ref "U5") (pin "H6") (pinfunction "PA5/UART0_RX/PWM0/PA_EINT5_H6") (pintype "passive"))
    )
    (net (code "125") (name "/UART0_TX") (class "Default")
      (node (ref "U5") (pin "F5") (pinfunction "PA4/UART0_TX/PA_EINT4_F5") (pintype "passive"))
    )
    (net (code "126") (name "/UART1_CTS") (class "Default")
      (node (ref "U5") (pin "E3") (pinfunction "PG9/UART1_CTS/PG_EINT9_E3") (pintype "passive"))
    )
    (net (code "127") (name "/UART1_RTS") (class "Default")
      (node (ref "U5") (pin "C3") (pinfunction "PG8/UART1_RTS/PG_EINT8_C3") (pintype "passive"))
    )
    (net (code "128") (name "/UART1_RX") (class "Default")
      (node (ref "U5") (pin "D3") (pinfunction "PG7/UART1_RX/PG_EINT7_D3") (pintype "passive"))
    )
    (net (code "129") (name "/UART1_TX") (class "Default")
      (node (ref "U5") (pin "G4") (pinfunction "PG6/UART1_TX/PG_EINT6_G4") (pintype "passive"))
    )
    (net (code "130") (name "/UART2_CTS") (class "Default")
      (node (ref "U5") (pin "E13") (pinfunction "PA3/UART2_CTS/JTAG_DI0/PA_EINT3_E13") (pintype "passive"))
    )
    (net (code "131") (name "/UART2_RTS") (class "Default")
      (node (ref "U5") (pin "D6") (pinfunction "PA2/UART2_RTS/JTAG_DO0/PA_EINT2_D6") (pintype "passive"))
    )
    (net (code "132") (name "/UART2_RX") (class "Default")
      (node (ref "U5") (pin "D5") (pinfunction "PA1/UART2_RX/JTAG_CK0/PA_EINT1_D5") (pintype "passive"))
    )
    (net (code "133") (name "/UART2_TX") (class "Default")
      (node (ref "U5") (pin "D11") (pinfunction "PA0/UART2_TX/JTAG_MS0/PA_EINT0_D11") (pintype "passive"))
    )
    (net (code "134") (name "/UART3_CTS") (class "Default")
      (node (ref "U5") (pin "D15") (pinfunction "PA16/SPI1_MISO/UART3_CTS/PA_EINT16_D15") (pintype "passive"))
    )
    (net (code "135") (name "/UART3_RTS") (class "Default")
      (node (ref "U5") (pin "F14") (pinfunction "PA15/SPI1_MOSI/UART3_RTS/PA_EINT15_F14") (pintype "passive"))
    )
    (net (code "136") (name "/UART3_RX") (class "Default")
      (node (ref "U5") (pin "G12") (pinfunction "PA14/SPI1_CLK/UART3_RX/PA_EINT14_G12") (pintype "passive"))
    )
    (net (code "137") (name "/UART3_TX") (class "Default")
      (node (ref "U5") (pin "E15") (pinfunction "PA13/SPI1_CS/UART3_TX/PA_EINT13_E15") (pintype "passive"))
    )
    (net (code "138") (name "/UBOOT") (class "Default")
      (node (ref "R22") (pin "1") (pinfunction "1_1") (pintype "passive"))
      (node (ref "U5") (pin "W6") (pinfunction "UBOOT_W6") (pintype "passive"))
    )
    (net (code "139") (name "/USB-DM0") (class "Default")
      (node (ref "U5") (pin "B5") (pinfunction "USB_DM0_B5") (pintype "passive"))
    )
    (net (code "140") (name "/USB-DM1") (class "Default")
      (node (ref "U5") (pin "B7") (pinfunction "USB_DM1_B7") (pintype "passive"))
    )
    (net (code "141") (name "/USB-DM2") (class "Default")
      (node (ref "U5") (pin "A8") (pinfunction "USB_DM2_A8") (pintype "passive"))
    )
    (net (code "142") (name "/USB-DM3") (class "Default")
      (node (ref "U5") (pin "B9") (pinfunction "USB_DM3_B9") (pintype "passive"))
    )
    (net (code "143") (name "/USB-DP0") (class "Default")
      (node (ref "U5") (pin "A5") (pinfunction "USB_DP0_A5") (pintype "passive"))
    )
    (net (code "144") (name "/USB-DP1") (class "Default")
      (node (ref "U5") (pin "B6") (pinfunction "USB_DP1_B6") (pintype "passive"))
    )
    (net (code "145") (name "/USB-DP2") (class "Default")
      (node (ref "U5") (pin "A7") (pinfunction "USB_DP2_A7") (pintype "passive"))
    )
    (net (code "146") (name "/USB-DP3") (class "Default")
      (node (ref "U5") (pin "B8") (pinfunction "USB_DP3_B8") (pintype "passive"))
    )
    (net (code "147") (name "/USB0-DRVVBUS") (class "Default")
      (node (ref "U5") (pin "P2") (pinfunction "PL2/S_UART_TX/S_PL_EINT2_P2") (pintype "passive"))
    )
    (net (code "148") (name "/VDD_CPUFB") (class "Default")
      (node (ref "R26") (pin "1") (pinfunction "1_1") (pintype "passive"))
      (node (ref "U5") (pin "T10") (pinfunction "VDD_CPUFB_T10") (pintype "power_in"))
    )
    (net (code "149") (name "/XIN") (class "Default")
      (node (ref "C32") (pin "2") (pinfunction "2_2") (pintype "passive"))
      (node (ref "U5") (pin "K2") (pinfunction "X24MIN_K2") (pintype "passive"))
      (node (ref "Y1") (pin "1") (pinfunction "XIN_1") (pintype "passive"))
    )
    (net (code "150") (name "/XOUT") (class "Default")
      (node (ref "C31") (pin "1") (pinfunction "1_1") (pintype "passive"))
      (node (ref "U5") (pin "K1") (pinfunction "X24MOUT_K1") (pintype "output"))
      (node (ref "Y1") (pin "3") (pinfunction "XOUT_3") (pintype "passive"))
    )
    (net (code "151") (name "AGND") (class "Default")
      (node (ref "C43") (pin "2") (pinfunction "2_2") (pintype "passive"))
      (node (ref "C44") (pin "1") (pinfunction "1_1") (pintype "passive"))
      (node (ref "C45") (pin "1") (pinfunction "1_1") (pintype "passive"))
      (node (ref "C46") (pin "1") (pinfunction "1_1") (pintype "passive"))
      (node (ref "R25") (pin "1") (pinfunction "1_1") (pintype "passive"))
      (node (ref "U5") (pin "U3") (pinfunction "AGND_U3") (pintype "power_in"))
    )
    (net (code "152") (name "GND") (class "Default")
      (node (ref "C13") (pin "1") (pinfunction "1_1") (pintype "passive"))
      (node (ref "C14") (pin "1") (pinfunction "1_1") (pintype "passive"))
      (node (ref "C15") (pin "1") (pinfunction "1_1") (pintype "passive"))
      (node (ref "C16") (pin "1") (pinfunction "1_1") (pintype "passive"))
      (node (ref "C17") (pin "1") (pinfunction "1_1") (pintype "passive"))
      (node (ref "C18") (pin "1") (pinfunction "1_1") (pintype "passive"))
      (node (ref "C19") (pin "1") (pinfunction "1_1") (pintype "passive"))
      (node (ref "C20") (pin "1") (pinfunction "1_1") (pintype "passive"))
      (node (ref "C21") (pin "1") (pinfunction "1_1") (pintype "passive"))
      (node (ref "C22") (pin "1") (pinfunction "1_1") (pintype "passive"))
      (node (ref "C24") (pin "1") (pinfunction "1_1") (pintype "passive"))
      (node (ref "C25") (pin "1") (pinfunction "1_1") (pintype "passive"))
      (node (ref "C26") (pin "1") (pinfunction "1_1") (pintype "passive"))
      (node (ref "C27") (pin "1") (pinfunction "1_1") (pintype "passive"))
      (node (ref "C28") (pin "1") (pinfunction "1_1") (pintype "passive"))
      (node (ref "C29") (pin "1") (pinfunction "1_1") (pintype "passive"))
      (node (ref "C30") (pin "1") (pinfunction "1_1") (pintype "passive"))
      (node (ref "C31") (pin "2") (pinfunction "2_2") (pintype "passive"))
      (node (ref "C32") (pin "1") (pinfunction "1_1") (pintype "passive"))
      (node (ref "C33") (pin "2") (pinfunction "2_2") (pintype "passive"))
      (node (ref "C34") (pin "1") (pinfunction "1_1") (pintype "passive"))
      (node (ref "C35") (pin "1") (pinfunction "1_1") (pintype "passive"))
      (node (ref "C36") (pin "1") (pinfunction "1_1") (pintype "passive"))
      (node (ref "C37") (pin "2") (pinfunction "2_2") (pintype "passive"))
      (node (ref "C38") (pin "1") (pinfunction "1_1") (pintype "passive"))
      (node (ref "C39") (pin "1") (pinfunction "1_1") (pintype "passive"))
      (node (ref "C40") (pin "1") (pinfunction "1_1") (pintype "passive"))
      (node (ref "C41") (pin "1") (pinfunction "1_1") (pintype "passive"))
      (node (ref "C42") (pin "1") (pinfunction "1_1") (pintype "passive"))
      (node (ref "C47") (pin "1") (pinfunction "1_1") (pintype "passive"))
      (node (ref "C48") (pin "2") (pinfunction "2_2") (pintype "passive"))
      (node (ref "C52") (pin "1") (pinfunction "1_1") (pintype "passive"))
      (node (ref "C53") (pin "1") (pinfunction "1_1") (pintype "passive"))
      (node (ref "R15") (pin "2") (pinfunction "2_2") (pintype "passive"))
      (node (ref "R16") (pin "2") (pinfunction "2_2") (pintype "passive"))
      (node (ref "R19") (pin "1") (pinfunction "1_1") (pintype "passive"))
      (node (ref "R20") (pin "2") (pinfunction "2_2") (pintype "passive"))
      (node (ref "R32") (pin "1") (pinfunction "1_1") (pintype "passive"))
      (node (ref "R33") (pin "1") (pinfunction "1_1") (pintype "passive"))
      (node (ref "U5") (pin "A20") (pinfunction "PD4/RGMII_RXCK/MII_RXCK/RMII_NULL_A20") (pintype "passive"))
      (node (ref "U5") (pin "A21") (pinfunction "GND_A21") (pintype "power_in"))
      (node (ref "U5") (pin "AA1") (pinfunction "GND_AA1") (pintype "power_in"))
      (node (ref "U5") (pin "B20") (pinfunction "PD2/RGMII_RXD1/MII_RXD1/RMII_RXD1_B20") (pintype "passive"))
      (node (ref "U5") (pin "B21") (pinfunction "PD6/RGMII_NULL/MII_RXERR/RMII_RXER_B21") (pintype "passive"))
      (node (ref "U5") (pin "C21") (pinfunction "PD0/RGMII_RXD3/MII_RXD3/RMII_NULL/DI_TX_C21") (pintype "passive"))
      (node (ref "U5") (pin "E18") (pinfunction "PD7/RGMII_TXD3/MII_TXD3/RMII_NULL_E18") (pintype "passive"))
      (node (ref "U5") (pin "E19") (pinfunction "PD12/RGMII_TXCK/MII_TXCK/RMII_TXCK_E19") (pintype "passive"))
      (node (ref "U5") (pin "E20") (pinfunction "PD8/RGMII_TXD2/MII_TXD2/RMII_NULL_E20") (pintype "passive"))
      (node (ref "U5") (pin "F19") (pinfunction "PD5/RGMII_RXCTL/MII_RXDV/RMII_CRS_DV_F19") (pintype "passive"))
      (node (ref "U5") (pin "F20") (pinfunction "PD11/RGMII_NULL/MII_CRS/RMII_NULL_F20") (pintype "passive"))
      (node (ref "U5") (pin "F21") (pinfunction "PD9/RGMII_TXD1/MII_TXD1/RMII_TXD1_F21") (pintype "passive"))
      (node (ref "U5") (pin "G8") (pinfunction "GND_G8") (pintype "power_in"))
      (node (ref "U5") (pin "H12") (pinfunction "GND_H12") (pintype "power_in"))
      (node (ref "U5") (pin "H15") (pinfunction "GND_H15") (pintype "power_in"))
      (node (ref "U5") (pin "H17") (pinfunction "PD1/RGMII_RXD2/MII_RXD2/RMII_NULL/DI_RX_H17") (pintype "passive"))
      (node (ref "U5") (pin "H18") (pinfunction "PD3/RGMII_RXD0/MII_RXD0/RMII_RXD0_H18") (pintype "passive"))
      (node (ref "U5") (pin "H19") (pinfunction "PD10/RGMII_TXD0/MII_TXD0/RMII_TXD0_H19") (pintype "passive"))
      (node (ref "U5") (pin "H8") (pinfunction "GND_TV_H8") (pintype "power_in"))
      (node (ref "U5") (pin "J13") (pinfunction "GND_J13") (pintype "power_in"))
      (node (ref "U5") (pin "J16") (pinfunction "GND_J16") (pintype "power_in"))
      (node (ref "U5") (pin "J9") (pinfunction "GND_J9") (pintype "power_in"))
      (node (ref "U5") (pin "K13") (pinfunction "GND_K13") (pintype "power_in"))
      (node (ref "U5") (pin "K14") (pinfunction "GND_K14") (pintype "power_in"))
      (node (ref "U5") (pin "K15") (pinfunction "GND_K15") (pintype "power_in"))
      (node (ref "U5") (pin "K16") (pinfunction "GND_K16") (pintype "power_in"))
      (node (ref "U5") (pin "K17") (pinfunction "PD13/RGMII_TXCTL/MII_TXEN/RMII_TXEN_K17") (pintype "passive"))
      (node (ref "U5") (pin "K18") (pinfunction "PD15/RGMII_CLKIN/MII_COL/RMII_NULL_K18") (pintype "passive"))
      (node (ref "U5") (pin "K7") (pinfunction "GND_K7") (pintype "power_in"))
      (node (ref "U5") (pin "K8") (pinfunction "GND_K8") (pintype "power_in"))
      (node (ref "U5") (pin "K9") (pinfunction "GND_K9") (pintype "power_in"))
      (node (ref "U5") (pin "L15") (pinfunction "GND_L15") (pintype "power_in"))
      (node (ref "U5") (pin "L17") (pinfunction "PD14/RGMII_NULL/MII_TXERR/RMII_NULL_L17") (pintype "passive"))
      (node (ref "U5") (pin "L18") (pinfunction "PD16/MDC_L18") (pintype "passive"))
      (node (ref "U5") (pin "L19") (pinfunction "PD17/MDIO_L19") (pintype "passive"))
      (node (ref "U5") (pin "L8") (pinfunction "GND_L8") (pintype "power_in"))
      (node (ref "U5") (pin "L9") (pinfunction "GND_L9") (pintype "power_in"))
      (node (ref "U5") (pin "M10") (pinfunction "GND_M10") (pintype "power_in"))
      (node (ref "U5") (pin "M11") (pinfunction "GND_M11") (pintype "power_in"))
      (node (ref "U5") (pin "M12") (pinfunction "GND_M12") (pintype "power_in"))
      (node (ref "U5") (pin "M13") (pinfunction "GND_M13") (pintype "power_in"))
      (node (ref "U5") (pin "M14") (pinfunction "GND_M14") (pintype "power_in"))
      (node (ref "U5") (pin "M15") (pinfunction "GND_M15") (pintype "power_in"))
      (node (ref "U5") (pin "M5") (pinfunction "HGND_M5") (pintype "power_in"))
      (node (ref "U5") (pin "M7") (pinfunction "GND_M7") (pintype "power_in"))
      (node (ref "U5") (pin "M8") (pinfunction "GND_M8") (pintype "power_in"))
      (node (ref "U5") (pin "M9") (pinfunction "GND_M9") (pintype "power_in"))
      (node (ref "U5") (pin "N10") (pinfunction "GND_N10") (pintype "power_in"))
      (node (ref "U5") (pin "N11") (pinfunction "GND_N11") (pintype "power_in"))
      (node (ref "U5") (pin "N12") (pinfunction "GND_N12") (pintype "power_in"))
      (node (ref "U5") (pin "N13") (pinfunction "GND_N13") (pintype "power_in"))
      (node (ref "U5") (pin "N14") (pinfunction "GND_N14") (pintype "power_in"))
      (node (ref "U5") (pin "N15") (pinfunction "GND_N15") (pintype "power_in"))
      (node (ref "U5") (pin "N7") (pinfunction "GND_N7") (pintype "power_in"))
      (node (ref "U5") (pin "N9") (pinfunction "GND_N9") (pintype "power_in"))
      (node (ref "U5") (pin "P10") (pinfunction "GND_P10") (pintype "power_in"))
      (node (ref "U5") (pin "P11") (pinfunction "GND_P11") (pintype "power_in"))
      (node (ref "U5") (pin "P12") (pinfunction "GND_P12") (pintype "power_in"))
      (node (ref "U5") (pin "P13") (pinfunction "GND_P13") (pintype "power_in"))
      (node (ref "U5") (pin "P14") (pinfunction "GND_P14") (pintype "power_in"))
      (node (ref "U5") (pin "P15") (pinfunction "GND_P15") (pintype "power_in"))
      (node (ref "U5") (pin "R10") (pinfunction "GND_R10") (pintype "power_in"))
      (node (ref "U5") (pin "R11") (pinfunction "GND_R11") (pintype "power_in"))
      (node (ref "U5") (pin "R12") (pinfunction "GND_R12") (pintype "power_in"))
      (node (ref "U5") (pin "R13") (pinfunction "GND_R13") (pintype "power_in"))
      (node (ref "U5") (pin "R14") (pinfunction "GND_R14") (pintype "power_in"))
      (node (ref "U5") (pin "R9") (pinfunction "GND_R9") (pintype "power_in"))
      (node (ref "U5") (pin "T11") (pinfunction "GND_T11") (pintype "power_in"))
      (node (ref "U5") (pin "T9") (pinfunction "GND_CPUXFB_T9") (pintype "power_in"))
      (node (ref "U6") (pin "A9") (pinfunction "VSS_A9") (pintype "passive"))
      (node (ref "U6") (pin "B1") (pinfunction "VSSQ_B1") (pintype "passive"))
      (node (ref "U6") (pin "B3") (pinfunction "VSS_B3") (pintype "passive"))
      (node (ref "U6") (pin "B9") (pinfunction "VSSQ_B9") (pintype "passive"))
      (node (ref "U6") (pin "D1") (pinfunction "VSSQ_D1") (pintype "passive"))
      (node (ref "U6") (pin "D8") (pinfunction "VSSQ_D8") (pintype "passive"))
      (node (ref "U6") (pin "E1") (pinfunction "VSS_E1") (pintype "passive"))
      (node (ref "U6") (pin "E2") (pinfunction "VSSQ_E2") (pintype "passive"))
      (node (ref "U6") (pin "E8") (pinfunction "VSSQ_E8") (pintype "passive"))
      (node (ref "U6") (pin "F9") (pinfunction "VSSQ_F9") (pintype "passive"))
      (node (ref "U6") (pin "G1") (pinfunction "VSSQ_G1") (pintype "passive"))
      (node (ref "U6") (pin "G8") (pinfunction "VSS_G8") (pintype "passive"))
      (node (ref "U6") (pin "G9") (pinfunction "VSSQ_G9") (pintype "passive"))
      (node (ref "U6") (pin "J2") (pinfunction "VSS_J2") (pintype "passive"))
      (node (ref "U6") (pin "J8") (pinfunction "VSS_J8") (pintype "passive"))
      (node (ref "U6") (pin "M1") (pinfunction "VSS_M1") (pintype "passive"))
      (node (ref "U6") (pin "M9") (pinfunction "VSS_M9") (pintype "passive"))
      (node (ref "U6") (pin "P1") (pinfunction "VSS_P1") (pintype "passive"))
      (node (ref "U6") (pin "P9") (pinfunction "VSS_P9") (pintype "passive"))
      (node (ref "U6") (pin "T1") (pinfunction "VSS_T1") (pintype "passive"))
      (node (ref "U6") (pin "T9") (pinfunction "VSS_T9") (pintype "passive"))
      (node (ref "Y1") (pin "2") (pinfunction "GND_2") (pintype "passive"))
      (node (ref "Y1") (pin "4") (pinfunction "GND_4") (pintype "passive"))
    )
    (net (code "153") (name "Net-(C50-Pad1)") (class "Default")
      (node (ref "C50") (pin "1") (pinfunction "1_1") (pintype "passive"))
      (node (ref "R31") (pin "1") (pinfunction "1_1") (pintype "passive"))
      (node (ref "R32") (pin "2") (pinfunction "2_2") (pintype "passive"))
    )
    (net (code "154") (name "Net-(C50-Pad2)") (class "Default")
      (node (ref "C50") (pin "2") (pinfunction "2_2") (pintype "passive"))
      (node (ref "R29") (pin "1") (pinfunction "1_1") (pintype "passive"))
      (node (ref "R30") (pin "2") (pinfunction "2_2") (pintype "passive"))
    )
    (net (code "155") (name "Net-(R16-Pad1)") (class "Default")
      (node (ref "R16") (pin "1") (pinfunction "1_1") (pintype "passive"))
      (node (ref "U6") (pin "L9") (pinfunction "NC_L9") (pintype "passive"))
    )
    (net (code "156") (name "Net-(U5-EPHY_RTX)") (class "Default")
      (node (ref "R33") (pin "2") (pinfunction "2_2") (pintype "passive"))
      (node (ref "U5") (pin "F6") (pinfunction "EPHY_RTX_F6") (pintype "passive"))
    )
    (net (code "157") (name "Net-(U5-NMI)") (class "Default")
      (node (ref "R28") (pin "2") (pinfunction "2_2") (pintype "passive"))
      (node (ref "U5") (pin "AA6") (pinfunction "NMI_AA6") (pintype "passive"))
    )
    (net (code "158") (name "Net-(U5-SZQ)") (class "Default")
      (node (ref "R20") (pin "1") (pinfunction "1_1") (pintype "passive"))
      (node (ref "U5") (pin "V10") (pinfunction "SZQ_V10") (pintype "passive"))
    )
    (net (code "159") (name "Net-(U5-VDD_EFUSEBP)") (class "Default")
      (node (ref "C33") (pin "1") (pinfunction "1_1") (pintype "passive"))
      (node (ref "U5") (pin "H11") (pinfunction "VDD_EFUSEBP_H11") (pintype "power_in"))
    )
    (net (code "160") (name "Net-(U5-VRA1)") (class "Default")
      (node (ref "C43") (pin "1") (pinfunction "1_1") (pintype "passive"))
      (node (ref "U5") (pin "Y4") (pinfunction "VRA1_Y4") (pintype "passive"))
    )
    (net (code "161") (name "Net-(U5-VRA2)") (class "Default")
      (node (ref "C44") (pin "2") (pinfunction "2_2") (pintype "passive"))
      (node (ref "R25") (pin "2") (pinfunction "2_2") (pintype "passive"))
      (node (ref "U5") (pin "W5") (pinfunction "VRA2_W5") (pintype "passive"))
    )
    (net (code "162") (name "Net-(U5-VRP)") (class "Default")
      (node (ref "C45") (pin "2") (pinfunction "2_2") (pintype "passive"))
      (node (ref "C46") (pin "2") (pinfunction "2_2") (pintype "passive"))
      (node (ref "U5") (pin "V4") (pinfunction "VRP_V4") (pintype "passive"))
    )
    (net (code "163") (name "Net-(U6-ZQ)") (class "Default")
      (node (ref "R15") (pin "1") (pinfunction "1_1") (pintype "passive"))
      (node (ref "U6") (pin "L8") (pinfunction "ZQ_L8") (pintype "passive"))
    )
    (net (code "164") (name "VCC-DRAM") (class "Default")
      (node (ref "C13") (pin "2") (pinfunction "2_2") (pintype "passive"))
      (node (ref "C14") (pin "2") (pinfunction "2_2") (pintype "passive"))
      (node (ref "C15") (pin "2") (pinfunction "2_2") (pintype "passive"))
      (node (ref "C16") (pin "2") (pinfunction "2_2") (pintype "passive"))
      (node (ref "C17") (pin "2") (pinfunction "2_2") (pintype "passive"))
      (node (ref "C18") (pin "2") (pinfunction "2_2") (pintype "passive"))
      (node (ref "C19") (pin "2") (pinfunction "2_2") (pintype "passive"))
      (node (ref "C20") (pin "2") (pinfunction "2_2") (pintype "passive"))
      (node (ref "C23") (pin "2") (pinfunction "2_2") (pintype "passive"))
      (node (ref "R17") (pin "2") (pinfunction "2_2") (pintype "passive"))
      (node (ref "U5") (pin "L16") (pinfunction "VCC-DRAM_L16") (pintype "power_in"))
      (node (ref "U5") (pin "M16") (pinfunction "VCC-DRAM_M16") (pintype "power_in"))
      (node (ref "U5") (pin "N16") (pinfunction "VCC-DRAM_N16") (pintype "power_in"))
      (node (ref "U5") (pin "P16") (pinfunction "VCC-DRAM_P16") (pintype "power_in"))
      (node (ref "U5") (pin "P17") (pinfunction "VCC-DRAM_P17") (pintype "power_in"))
      (node (ref "U5") (pin "R16") (pinfunction "VCC-DRAM_R16") (pintype "power_in"))
      (node (ref "U5") (pin "T12") (pinfunction "VCC-DRAM_T12") (pintype "power_in"))
      (node (ref "U5") (pin "T13") (pinfunction "VCC-DRAM_T13") (pintype "power_in"))
      (node (ref "U5") (pin "T14") (pinfunction "VCC-DRAM_T14") (pintype "power_in"))
      (node (ref "U5") (pin "T15") (pinfunction "VCC-DRAM_T15") (pintype "power_in"))
      (node (ref "U5") (pin "U11") (pinfunction "VCC-DRAM_U11") (pintype "power_in"))
      (node (ref "U6") (pin "A1") (pinfunction "VDDQ_A1") (pintype "passive"))
      (node (ref "U6") (pin "A8") (pinfunction "VDDQ_A8") (pintype "passive"))
      (node (ref "U6") (pin "B2") (pinfunction "VDD_B2") (pintype "passive"))
      (node (ref "U6") (pin "C1") (pinfunction "VDDQ_C1") (pintype "passive"))
      (node (ref "U6") (pin "C9") (pinfunction "VDDQ_C9") (pintype "passive"))
      (node (ref "U6") (pin "D2") (pinfunction "VDDQ_D2") (pintype "passive"))
      (node (ref "U6") (pin "D9") (pinfunction "VDD_D9") (pintype "passive"))
      (node (ref "U6") (pin "E9") (pinfunction "VDDQ_E9") (pintype "passive"))
      (node (ref "U6") (pin "F1") (pinfunction "VDDQ_F1") (pintype "passive"))
      (node (ref "U6") (pin "G7") (pinfunction "VDD_G7") (pintype "passive"))
      (node (ref "U6") (pin "H2") (pinfunction "VDDQ_H2") (pintype "passive"))
      (node (ref "U6") (pin "H9") (pinfunction "VDDQ_H9") (pintype "passive"))
      (node (ref "U6") (pin "K2") (pinfunction "VDD_K2") (pintype "passive"))
      (node (ref "U6") (pin "K8") (pinfunction "VDD_K8") (pintype "passive"))
      (node (ref "U6") (pin "N1") (pinfunction "VDD_N1") (pintype "passive"))
      (node (ref "U6") (pin "N9") (pinfunction "VDD_N9") (pintype "passive"))
      (node (ref "U6") (pin "R1") (pinfunction "VDD_R1") (pintype "passive"))
      (node (ref "U6") (pin "R9") (pinfunction "VDD_R9") (pintype "passive"))
    )
    (net (code "165") (name "VDD-CPUS") (class "Default")
      (node (ref "C29") (pin "2") (pinfunction "2_2") (pintype "passive"))
      (node (ref "C30") (pin "2") (pinfunction "2_2") (pintype "passive"))
      (node (ref "U5") (pin "J7") (pinfunction "VDD_CPUS_J7") (pintype "power_in"))
      (node (ref "U5") (pin "J8") (pinfunction "VDD_CPUS_J8") (pintype "power_in"))
      (node (ref "U5") (pin "M4") (pinfunction "RTC_VIO_M4") (pintype "power_in"))
    )
    (net (code "166") (name "VDD-CPUX") (class "Default")
      (node (ref "C39") (pin "2") (pinfunction "2_2") (pintype "passive"))
      (node (ref "C40") (pin "2") (pinfunction "2_2") (pintype "passive"))
      (node (ref "C41") (pin "2") (pinfunction "2_2") (pintype "passive"))
      (node (ref "R26") (pin "2") (pinfunction "2_2") (pintype "passive"))
      (node (ref "U5") (pin "N8") (pinfunction "VDD_CPUX_N8") (pintype "power_in"))
      (node (ref "U5") (pin "P6") (pinfunction "VDD_CPUX_P6") (pintype "power_in"))
      (node (ref "U5") (pin "P7") (pinfunction "VDD_CPUX_P7") (pintype "power_in"))
      (node (ref "U5") (pin "P8") (pinfunction "VDD_CPUX_P8") (pintype "power_in"))
      (node (ref "U5") (pin "P9") (pinfunction "VDD_CPUX_P9") (pintype "power_in"))
      (node (ref "U5") (pin "R6") (pinfunction "VDD_CPUX_R6") (pintype "power_in"))
      (node (ref "U5") (pin "R7") (pinfunction "VDD_CPUX_R7") (pintype "power_in"))
      (node (ref "U5") (pin "R8") (pinfunction "VDD_CPUX_R8") (pintype "power_in"))
      (node (ref "U5") (pin "T6") (pinfunction "VDD_CPUX_T6") (pintype "power_in"))
      (node (ref "U5") (pin "T7") (pinfunction "VDD_CPUX_T7") (pintype "power_in"))
      (node (ref "U5") (pin "T8") (pinfunction "VDD_CPUX_T8") (pintype "power_in"))
      (node (ref "U5") (pin "U6") (pinfunction "VDD_CPUX_U6") (pintype "power_in"))
      (node (ref "U5") (pin "U9") (pinfunction "VDD_CPUX_U9") (pintype "power_in"))
    )
    (net (code "167") (name "VDD1V1-EPHY") (class "Default")
      (node (ref "C38") (pin "2") (pinfunction "2_2") (pintype "passive"))
      (node (ref "U5") (pin "F8") (pinfunction "EPHY_VDD_F8") (pintype "power_in"))
    )
    (net (code "168") (name "VDD1V2-SYS") (class "Default")
      (node (ref "C34") (pin "2") (pinfunction "2_2") (pintype "passive"))
      (node (ref "C35") (pin "2") (pinfunction "2_2") (pintype "passive"))
      (node (ref "C36") (pin "2") (pinfunction "2_2") (pintype "passive"))
      (node (ref "U5") (pin "H10") (pinfunction "VDD_SYS_H10") (pintype "power_in"))
      (node (ref "U5") (pin "J10") (pinfunction "VDD_SYS_J10") (pintype "power_in"))
      (node (ref "U5") (pin "J11") (pinfunction "VDD_SYS_J11") (pintype "power_in"))
      (node (ref "U5") (pin "J12") (pinfunction "VDD_SYS_J12") (pintype "power_in"))
      (node (ref "U5") (pin "K10") (pinfunction "VDD_SYS_K10") (pintype "power_in"))
      (node (ref "U5") (pin "K11") (pinfunction "VDD_SYS_K11") (pintype "power_in"))
      (node (ref "U5") (pin "K12") (pinfunction "VDD_SYS_K12") (pintype "power_in"))
      (node (ref "U5") (pin "L10") (pinfunction "VDD_SYS_L10") (pintype "power_in"))
      (node (ref "U5") (pin "L11") (pinfunction "VDD_SYS_L11") (pintype "power_in"))
      (node (ref "U5") (pin "L12") (pinfunction "VDD_SYS_L12") (pintype "power_in"))
      (node (ref "U5") (pin "L13") (pinfunction "VDD_SYS_L13") (pintype "power_in"))
      (node (ref "U5") (pin "L14") (pinfunction "VDD_SYS_L14") (pintype "power_in"))
    )
    (net (code "169") (name "VDD_AV_3.3V") (class "Default")
      (node (ref "C37") (pin "1") (pinfunction "1_1") (pintype "passive"))
      (node (ref "C42") (pin "2") (pinfunction "2_2") (pintype "passive"))
      (node (ref "R21") (pin "2") (pinfunction "2_2") (pintype "passive"))
      (node (ref "R22") (pin "2") (pinfunction "2_2") (pintype "passive"))
      (node (ref "R23") (pin "2") (pinfunction "2_2") (pintype "passive"))
      (node (ref "R24") (pin "2") (pinfunction "2_2") (pintype "passive"))
      (node (ref "R27") (pin "1") (pinfunction "1_1") (pintype "passive"))
      (node (ref "R28") (pin "1") (pinfunction "1_1") (pintype "passive"))
      (node (ref "U5") (pin "G9") (pinfunction "V33_TV_G9") (pintype "power_in"))
      (node (ref "U5") (pin "K6") (pinfunction "VCC_RTC_K6") (pintype "power_in"))
      (node (ref "U5") (pin "N3") (pinfunction "VCC_PLL_N3") (pintype "power_in"))
      (node (ref "U5") (pin "V3") (pinfunction "AVCC_V3") (pintype "power_in"))
    )
    (net (code "170") (name "VDD_SYS_3.3V") (class "Default")
      (node (ref "C25") (pin "2") (pinfunction "2_2") (pintype "passive"))
      (node (ref "C26") (pin "2") (pinfunction "2_2") (pintype "passive"))
      (node (ref "C27") (pin "2") (pinfunction "2_2") (pintype "passive"))
      (node (ref "C28") (pin "2") (pinfunction "2_2") (pintype "passive"))
      (node (ref "U5") (pin "G10") (pinfunction "VDD_EFUSE_G10") (pintype "power_in"))
      (node (ref "U5") (pin "G11") (pinfunction "VCC_USB_G11") (pintype "power_in"))
      (node (ref "U5") (pin "G13") (pinfunction "VCC_IO_G13") (pintype "power_in"))
      (node (ref "U5") (pin "G14") (pinfunction "VCC_IO_G14") (pintype "power_in"))
      (node (ref "U5") (pin "G15") (pinfunction "VCC_IO_G15") (pintype "power_in"))
      (node (ref "U5") (pin "G7") (pinfunction "EPHY_VCC_G7") (pintype "power_in"))
      (node (ref "U5") (pin "H13") (pinfunction "VCC_IO_H13") (pintype "power_in"))
      (node (ref "U5") (pin "H14") (pinfunction "VCC_IO_H14") (pintype "power_in"))
      (node (ref "U5") (pin "H7") (pinfunction "VCC_PG_H7") (pintype "power_in"))
      (node (ref "U5") (pin "J14") (pinfunction "VCC_IO_J14") (pintype "power_in"))
      (node (ref "U5") (pin "J15") (pinfunction "VCC_PD_J15") (pintype "power_in"))
      (node (ref "U5") (pin "J6") (pinfunction "HVCC_J6") (pintype "power_in"))
    )
    (net (code "171") (name "unconnected-(U5-JTAG-SEL0-PadA1)") (class "Default")
      (node (ref "U5") (pin "A1") (pinfunction "JTAG-SEL0_A1") (pintype "passive"))
    )
    (net (code "172") (name "unconnected-(U5-JTAG-SEL1-PadB2)") (class "Default")
      (node (ref "U5") (pin "B2") (pinfunction "JTAG-SEL1_B2") (pintype "passive"))
    )
    (net (code "173") (name "unconnected-(U5-MICIN2N-PadAA2)") (class "Default")
      (node (ref "U5") (pin "AA2") (pinfunction "MICIN2N_AA2") (pintype "passive"))
    )
    (net (code "174") (name "unconnected-(U5-MICIN2P-PadY2)") (class "Default")
      (node (ref "U5") (pin "Y2") (pinfunction "MICIN2P_Y2") (pintype "passive"))
    )
    (net (code "175") (name "unconnected-(U5-NC-PadK4)") (class "Default")
      (node (ref "U5") (pin "K4") (pinfunction "NC_K4") (pintype "passive"))
    )
    (net (code "176") (name "unconnected-(U5-PA6{slash}SIM_PWREN{slash}PWM1{slash}PA_EINT6-PadE14)") (class "Default")
      (node (ref "U5") (pin "E14") (pinfunction "PA6/SIM_PWREN/PWM1/PA_EINT6_E14") (pintype "passive"))
    )
    (net (code "177") (name "unconnected-(U5-PA7{slash}SIM_CLK{slash}PA_EINT7-PadD8)") (class "Default")
      (node (ref "U5") (pin "D8") (pinfunction "PA7/SIM_CLK/PA_EINT7_D8") (pintype "passive"))
    )
    (net (code "178") (name "unconnected-(U5-PA8{slash}SIM_DATA{slash}PA_EINT8-PadF13)") (class "Default")
      (node (ref "U5") (pin "F13") (pinfunction "PA8/SIM_DATA/PA_EINT8_F13") (pintype "passive"))
    )
    (net (code "179") (name "unconnected-(U5-PA9{slash}SIM_RST{slash}PA_EINT9-PadD13)") (class "Default")
      (node (ref "U5") (pin "D13") (pinfunction "PA9/SIM_RST/PA_EINT9_D13") (pintype "passive"))
    )
    (net (code "180") (name "unconnected-(U5-PA17{slash}SPDIF_OUT(OWA_OUT){slash}PA_EINT17-PadC14)") (class "Default")
      (node (ref "U5") (pin "C14") (pinfunction "PA17/SPDIF_OUT(OWA_OUT)/PA_EINT17_C14") (pintype "passive"))
    )
    (net (code "181") (name "unconnected-(U5-PA20{slash}PCM0_DOUT{slash}SIM_VPPEN{slash}PA_EINT20-PadA13)") (class "Default")
      (node (ref "U5") (pin "A13") (pinfunction "PA20/PCM0_DOUT/SIM_VPPEN/PA_EINT20_A13") (pintype "passive"))
    )
    (net (code "182") (name "unconnected-(U5-PA21{slash}PCM0_DIN{slash}SIM_VPPPP{slash}PA_EINT21-PadA14)") (class "Default")
      (node (ref "U5") (pin "A14") (pinfunction "PA21/PCM0_DIN/SIM_VPPPP/PA_EINT21_A14") (pintype "passive"))
    )
    (net (code "183") (name "unconnected-(U5-PC4{slash}NAND_CE0-PadF16)") (class "Default")
      (node (ref "U5") (pin "F16") (pinfunction "PC4/NAND_CE0_F16") (pintype "passive"))
    )
    (net (code "184") (name "unconnected-(U5-PC5{slash}NAND_RE{slash}SDC2_CLK-PadA17)") (class "Default")
      (node (ref "U5") (pin "A17") (pinfunction "PC5/NAND_RE/SDC2_CLK_A17") (pintype "passive"))
    )
    (net (code "185") (name "unconnected-(U5-PC6{slash}NAND_RB0{slash}SDC2_CMD-PadE16)") (class "Default")
      (node (ref "U5") (pin "E16") (pinfunction "PC6/NAND_RB0/SDC2_CMD_E16") (pintype "passive"))
    )
    (net (code "186") (name "unconnected-(U5-PC7{slash}NAND_RB1-PadA16)") (class "Default")
      (node (ref "U5") (pin "A16") (pinfunction "PC7/NAND_RB1_A16") (pintype "passive"))
    )
    (net (code "187") (name "unconnected-(U5-PC8{slash}NAND_DQ0{slash}SDC2_D0-PadB18)") (class "Default")
      (node (ref "U5") (pin "B18") (pinfunction "PC8/NAND_DQ0/SDC2_D0_B18") (pintype "passive"))
    )
    (net (code "188") (name "unconnected-(U5-PC9{slash}NAND_DQ1{slash}SDC2_D1-PadC17)") (class "Default")
      (node (ref "U5") (pin "C17") (pinfunction "PC9/NAND_DQ1/SDC2_D1_C17") (pintype "passive"))
    )
    (net (code "189") (name "unconnected-(U5-PC10{slash}NAND_DQ2{slash}SDC2_D2-PadD17)") (class "Default")
      (node (ref "U5") (pin "D17") (pinfunction "PC10/NAND_DQ2/SDC2_D2_D17") (pintype "passive"))
    )
    (net (code "190") (name "unconnected-(U5-PC11{slash}NAND_DQ3{slash}SDC2_D3-PadC18)") (class "Default")
      (node (ref "U5") (pin "C18") (pinfunction "PC11/NAND_DQ3/SDC2_D3_C18") (pintype "passive"))
    )
    (net (code "191") (name "unconnected-(U5-PC12{slash}NAND_DQ4{slash}SDC2_D4-PadB17)") (class "Default")
      (node (ref "U5") (pin "B17") (pinfunction "PC12/NAND_DQ4/SDC2_D4_B17") (pintype "passive"))
    )
    (net (code "192") (name "unconnected-(U5-PC13{slash}NAND_DQ5{slash}SDC2_D5-PadB19)") (class "Default")
      (node (ref "U5") (pin "B19") (pinfunction "PC13/NAND_DQ5/SDC2_D5_B19") (pintype "passive"))
    )
    (net (code "193") (name "unconnected-(U5-PC14{slash}NAND_DQ6{slash}SDC2_D6-PadF17)") (class "Default")
      (node (ref "U5") (pin "F17") (pinfunction "PC14/NAND_DQ6/SDC2_D6_F17") (pintype "passive"))
    )
    (net (code "194") (name "unconnected-(U5-PC15{slash}NAND_DQ7{slash}SDC2_D7-PadC19)") (class "Default")
      (node (ref "U5") (pin "C19") (pinfunction "PC15/NAND_DQ7/SDC2_D7_C19") (pintype "passive"))
    )
    (net (code "195") (name "unconnected-(U5-PC16{slash}NAND_DQS{slash}SDC2_RST-PadH16)") (class "Default")
      (node (ref "U5") (pin "H16") (pinfunction "PC16/NAND_DQS/SDC2_RST_H16") (pintype "passive"))
    )
    (net (code "196") (name "unconnected-(U5-PG0{slash}SDC1_CLK{slash}PG_EINT0-PadJ3)") (class "Default")
      (node (ref "U5") (pin "J3") (pinfunction "PG0/SDC1_CLK/PG_EINT0_J3") (pintype "passive"))
    )
    (net (code "197") (name "unconnected-(U5-PG1{slash}SDC1_CMD{slash}PG_EINT1-PadL2)") (class "Default")
      (node (ref "U5") (pin "L2") (pinfunction "PG1/SDC1_CMD/PG_EINT1_L2") (pintype "passive"))
    )
    (net (code "198") (name "unconnected-(U5-PG2{slash}SDC1_D0{slash}PG_EINT2-PadH4)") (class "Default")
      (node (ref "U5") (pin "H4") (pinfunction "PG2/SDC1_D0/PG_EINT2_H4") (pintype "passive"))
    )
    (net (code "199") (name "unconnected-(U5-PG3{slash}SDC1_D1{slash}PG_EINT3-PadF3)") (class "Default")
      (node (ref "U5") (pin "F3") (pinfunction "PG3/SDC1_D1/PG_EINT3_F3") (pintype "passive"))
    )
    (net (code "200") (name "unconnected-(U5-PG4{slash}SDC1_D2{slash}PG_EINT4-PadC2)") (class "Default")
      (node (ref "U5") (pin "C2") (pinfunction "PG4/SDC1_D2/PG_EINT4_C2") (pintype "passive"))
    )
    (net (code "201") (name "unconnected-(U5-PG5{slash}SDC1_D3{slash}PG_EINT5-PadC1)") (class "Default")
      (node (ref "U5") (pin "C1") (pinfunction "PG5/SDC1_D3/PG_EINT5_C1") (pintype "passive"))
    )
    (net (code "202") (name "unconnected-(U5-PG10{slash}PCM1_SYNC{slash}PG_EINT10-PadM3)") (class "Default")
      (node (ref "U5") (pin "M3") (pinfunction "PG10/PCM1_SYNC/PG_EINT10_M3") (pintype "passive"))
    )
    (net (code "203") (name "unconnected-(U5-PG13{slash}PCM1_DIN{slash}PG_EINT13-PadB1)") (class "Default")
      (node (ref "U5") (pin "B1") (pinfunction "PG13/PCM1_DIN/PG_EINT13_B1") (pintype "passive"))
    )
    (net (code "204") (name "unconnected-(U5-PL0{slash}S_TWI_SCK{slash}S_PL_EINT0-PadN1)") (class "Default")
      (node (ref "U5") (pin "N1") (pinfunction "PL0/S_TWI_SCK/S_PL_EINT0_N1") (pintype "passive"))
    )
    (net (code "205") (name "unconnected-(U5-PL1{slash}S_TWI_SDA{slash}S_PL_EINT1-PadM1)") (class "Default")
      (node (ref "U5") (pin "M1") (pinfunction "PL1/S_TWI_SDA/S_PL_EINT1_M1") (pintype "passive"))
    )
    (net (code "206") (name "unconnected-(U5-PL5{slash}S_JTAG_CK{slash}S_PL_EINT5-PadR2)") (class "Default")
      (node (ref "U5") (pin "R2") (pinfunction "PL5/S_JTAG_CK/S_PL_EINT5_R2") (pintype "passive"))
    )
    (net (code "207") (name "unconnected-(U5-PL6{slash}S_JTAG_DO{slash}S_PL_EINT6-PadT4)") (class "Default")
      (node (ref "U5") (pin "T4") (pinfunction "PL6/S_JTAG_DO/S_PL_EINT6_T4") (pintype "passive"))
    )
    (net (code "208") (name "unconnected-(U5-PL7{slash}S_JTAG_DI{slash}S_PL_EINT7-PadT3)") (class "Default")
      (node (ref "U5") (pin "T3") (pinfunction "PL7/S_JTAG_DI/S_PL_EINT7_T3") (pintype "passive"))
    )
    (net (code "209") (name "unconnected-(U5-PLLTEST-PadL5)") (class "Default")
      (node (ref "U5") (pin "L5") (pinfunction "PLLTEST_L5") (pintype "passive"))
    )
    (net (code "210") (name "unconnected-(U5-SDQ16-PadY17)") (class "Default")
      (node (ref "U5") (pin "Y17") (pinfunction "SDQ16_Y17") (pintype "passive"))
    )
    (net (code "211") (name "unconnected-(U5-SDQ17-PadAA17)") (class "Default")
      (node (ref "U5") (pin "AA17") (pinfunction "SDQ17_AA17") (pintype "passive"))
    )
    (net (code "212") (name "unconnected-(U5-SDQ18-PadY16)") (class "Default")
      (node (ref "U5") (pin "Y16") (pinfunction "SDQ18_Y16") (pintype "passive"))
    )
    (net (code "213") (name "unconnected-(U5-SDQ19-PadW15)") (class "Default")
      (node (ref "U5") (pin "W15") (pinfunction "SDQ19_W15") (pintype "passive"))
    )
    (net (code "214") (name "unconnected-(U5-SDQ20-PadY14)") (class "Default")
      (node (ref "U5") (pin "Y14") (pinfunction "SDQ20_Y14") (pintype "passive"))
    )
    (net (code "215") (name "unconnected-(U5-SDQ21-PadAA14)") (class "Default")
      (node (ref "U5") (pin "AA14") (pinfunction "SDQ21_AA14") (pintype "passive"))
    )
    (net (code "216") (name "unconnected-(U5-SDQ22-PadY13)") (class "Default")
      (node (ref "U5") (pin "Y13") (pinfunction "SDQ22_Y13") (pintype "passive"))
    )
    (net (code "217") (name "unconnected-(U5-SDQ23-PadY12)") (class "Default")
      (node (ref "U5") (pin "Y12") (pinfunction "SDQ23_Y12") (pintype "passive"))
    )
    (net (code "218") (name "unconnected-(U5-SDQ24-PadW12)") (class "Default")
      (node (ref "U5") (pin "W12") (pinfunction "SDQ24_W12") (pintype "passive"))
    )
    (net (code "219") (name "unconnected-(U5-SDQ25-PadAA11)") (class "Default")
      (node (ref "U5") (pin "AA11") (pinfunction "SDQ25_AA11") (pintype "passive"))
    )
    (net (code "220") (name "unconnected-(U5-SDQ26-PadY11)") (class "Default")
      (node (ref "U5") (pin "Y11") (pinfunction "SDQ26_Y11") (pintype "passive"))
    )
    (net (code "221") (name "unconnected-(U5-SDQ27-PadY10)") (class "Default")
      (node (ref "U5") (pin "Y10") (pinfunction "SDQ27_Y10") (pintype "passive"))
    )
    (net (code "222") (name "unconnected-(U5-SDQ28-PadW9)") (class "Default")
      (node (ref "U5") (pin "W9") (pinfunction "SDQ28_W9") (pintype "passive"))
    )
    (net (code "223") (name "unconnected-(U5-SDQ29-PadAA8)") (class "Default")
      (node (ref "U5") (pin "AA8") (pinfunction "SDQ29_AA8") (pintype "passive"))
    )
    (net (code "224") (name "unconnected-(U5-SDQ30-PadY8)") (class "Default")
      (node (ref "U5") (pin "Y8") (pinfunction "SDQ30_Y8") (pintype "passive"))
    )
    (net (code "225") (name "unconnected-(U5-SDQ31-PadY7)") (class "Default")
      (node (ref "U5") (pin "Y7") (pinfunction "SDQ31_Y7") (pintype "passive"))
    )
    (net (code "226") (name "unconnected-(U5-SDQM2-PadAA18)") (class "Default")
      (node (ref "U5") (pin "AA18") (pinfunction "SDQM2_AA18") (pintype "output"))
    )
    (net (code "227") (name "unconnected-(U5-SDQM3-PadAA12)") (class "Default")
      (node (ref "U5") (pin "AA12") (pinfunction "SDQM3_AA12") (pintype "output"))
    )
    (net (code "228") (name "unconnected-(U5-SDQS2-PadAA15)") (class "Default")
      (node (ref "U5") (pin "AA15") (pinfunction "SDQS2_AA15") (pintype "passive"))
    )
    (net (code "229") (name "unconnected-(U5-SDQS2B-PadY15)") (class "Default")
      (node (ref "U5") (pin "Y15") (pinfunction "SDQS2B_Y15") (pintype "passive"))
    )
    (net (code "230") (name "unconnected-(U5-SDQS3-PadAA9)") (class "Default")
      (node (ref "U5") (pin "AA9") (pinfunction "SDQS3_AA9") (pintype "passive"))
    )
    (net (code "231") (name "unconnected-(U5-SDQS3B-PadY9)") (class "Default")
      (node (ref "U5") (pin "Y9") (pinfunction "SDQS3B_Y9") (pintype "passive"))
    )
    (net (code "232") (name "unconnected-(U5-TEST-PadT5)") (class "Default")
      (node (ref "U5") (pin "T5") (pinfunction "TEST_T5") (pintype "passive"))
    )
    (net (code "233") (name "unconnected-(U5-TVOUT-PadF10)") (class "Default")
      (node (ref "U5") (pin "F10") (pinfunction "TVOUT_F10") (pintype "output"))
    )
    (net (code "234") (name "unconnected-(U5-X32KFOUT-PadP3)") (class "Default")
      (node (ref "U5") (pin "P3") (pinfunction "X32KFOUT_P3") (pintype "output"))
    )
    (net (code "235") (name "unconnected-(U5-X32KIN-PadV5)") (class "Default")
      (node (ref "U5") (pin "V5") (pinfunction "X32KIN_V5") (pintype "passive"))
    )
    (net (code "236") (name "unconnected-(U5-X32KOUT-PadU4)") (class "Default")
      (node (ref "U5") (pin "U4") (pinfunction "X32KOUT_U4") (pintype "output"))
    )
  )
)
